# axiom_beta_plugin_module_TE0714_SDI_v0_7.net
KiCad netlist of a schematic drawn in EAGLE
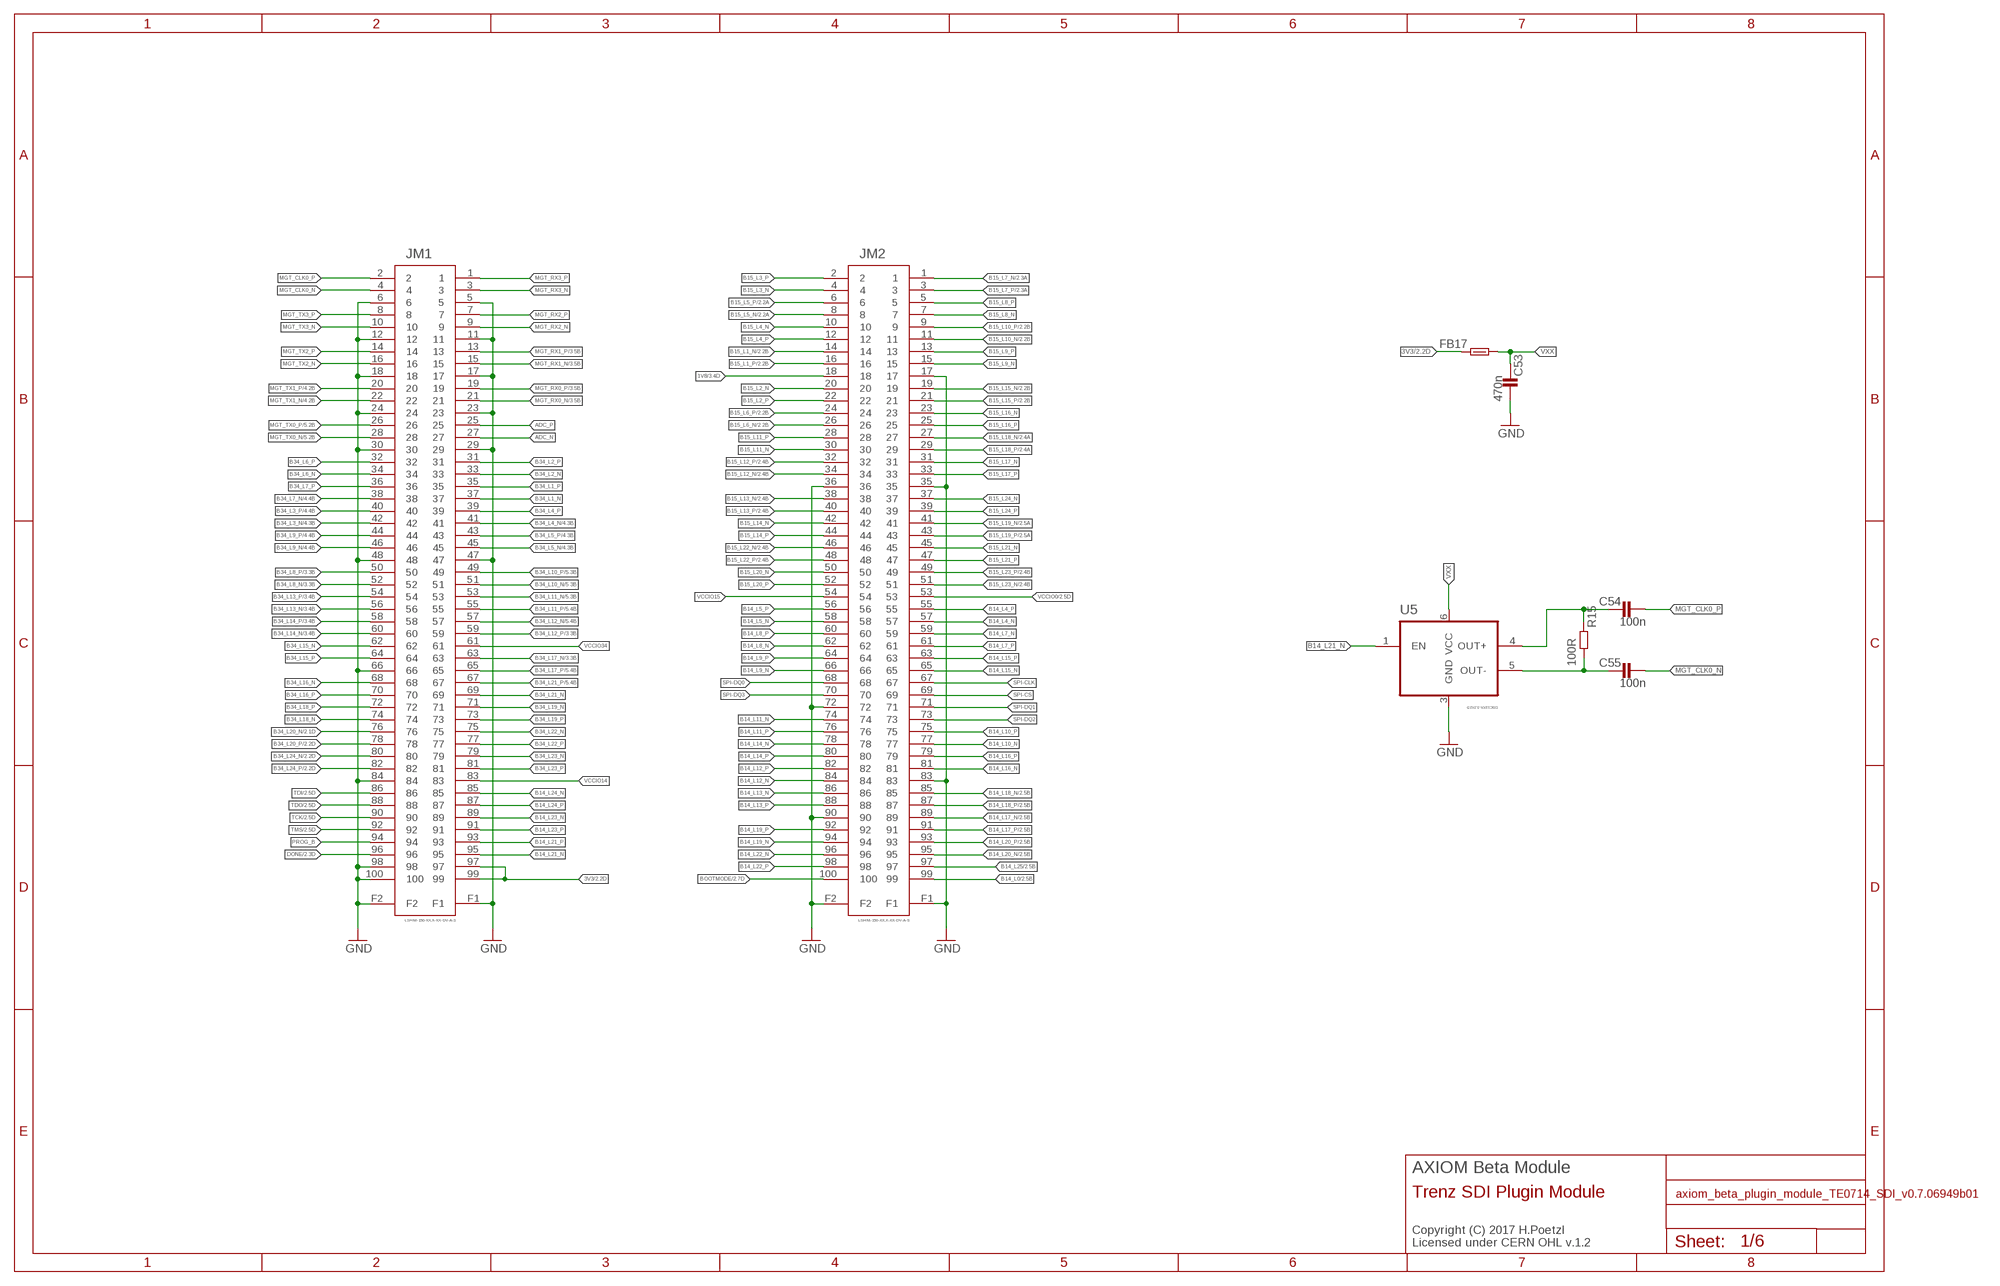
[diagram p0: schematic, sheet 1]
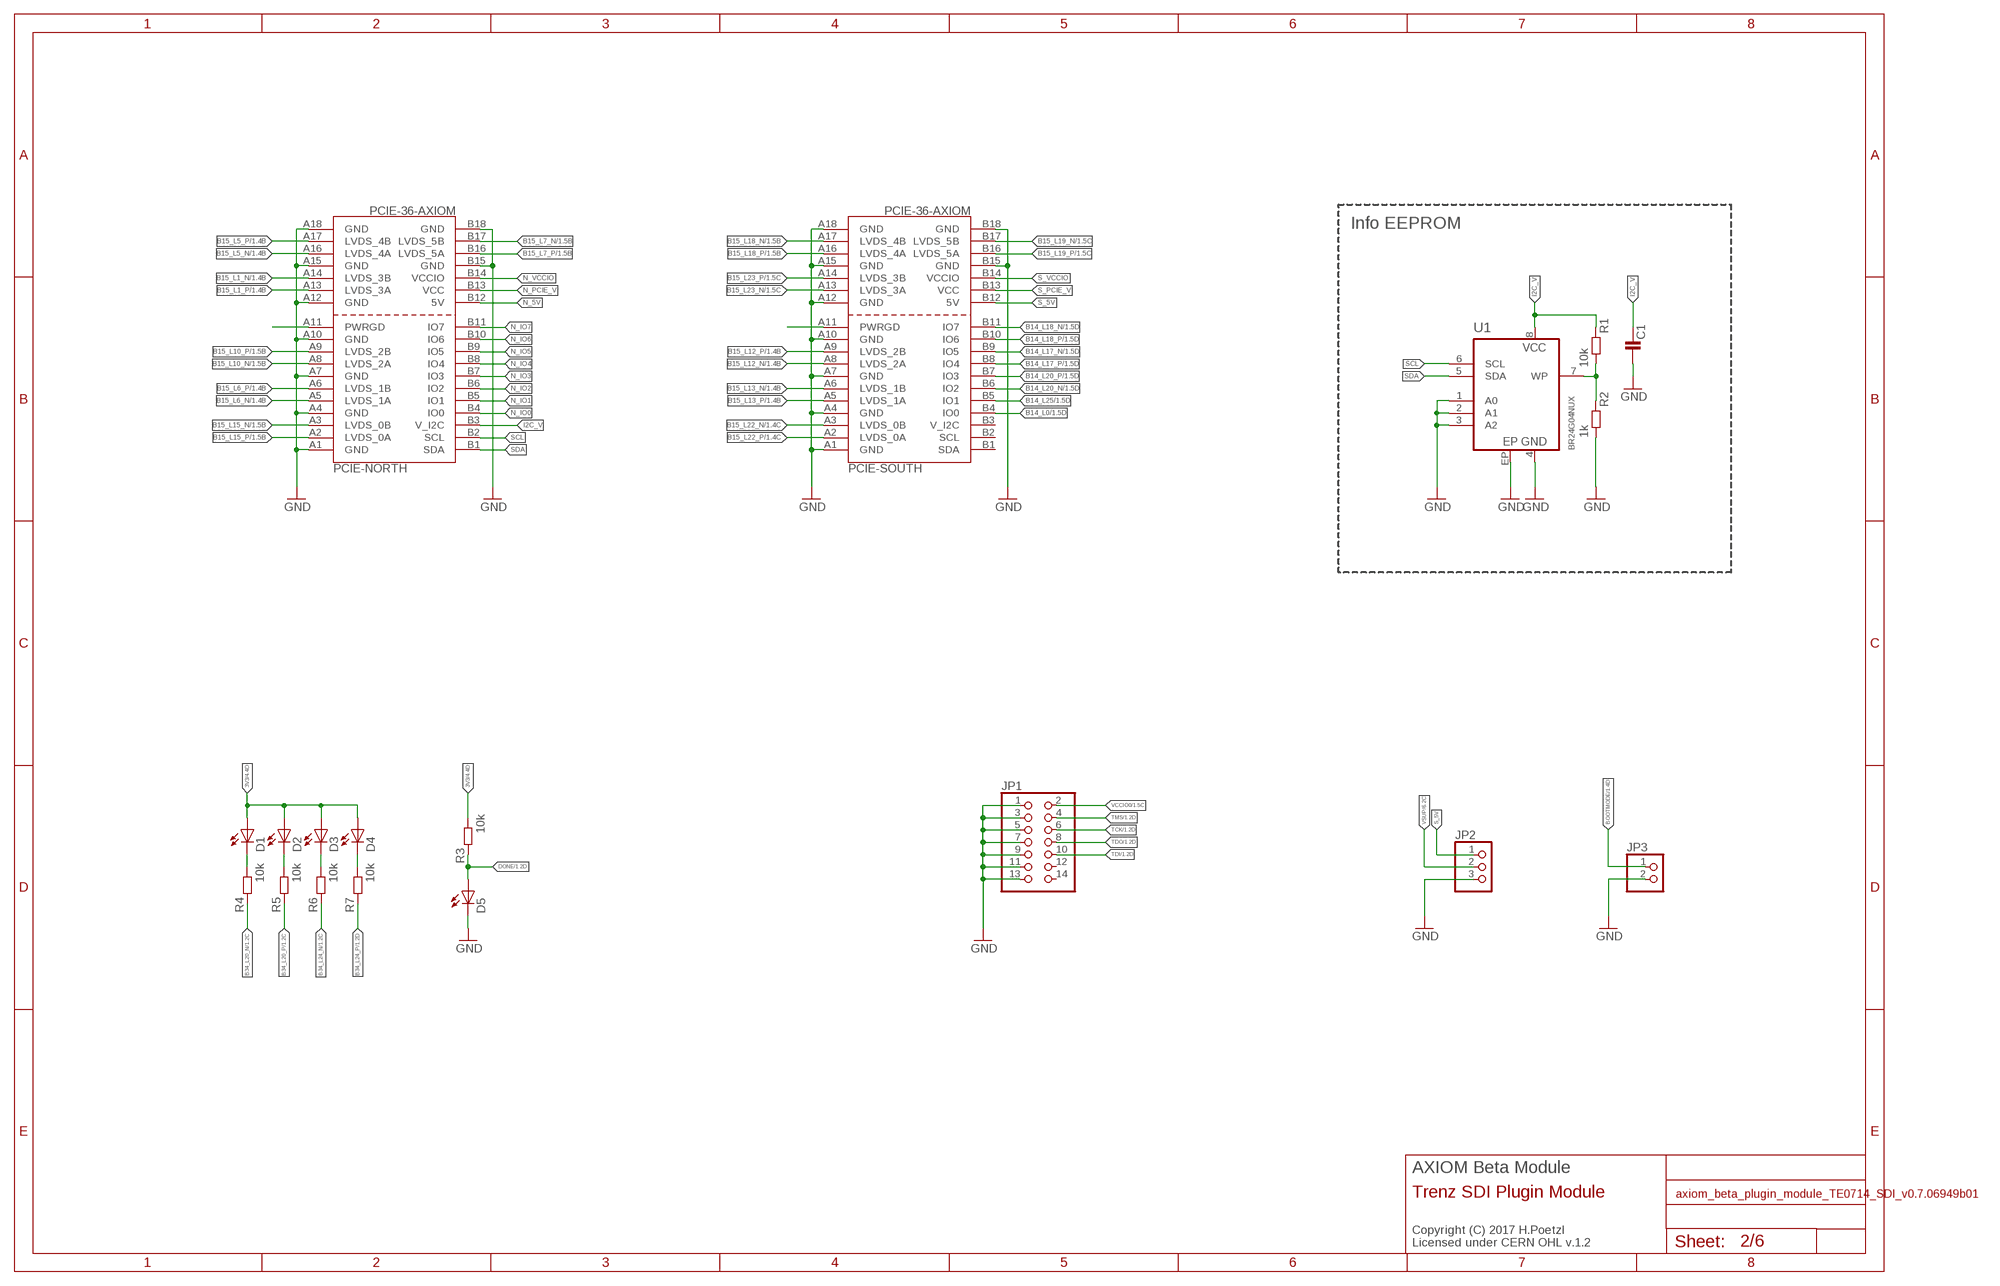
[diagram p1: schematic, sheet 2]
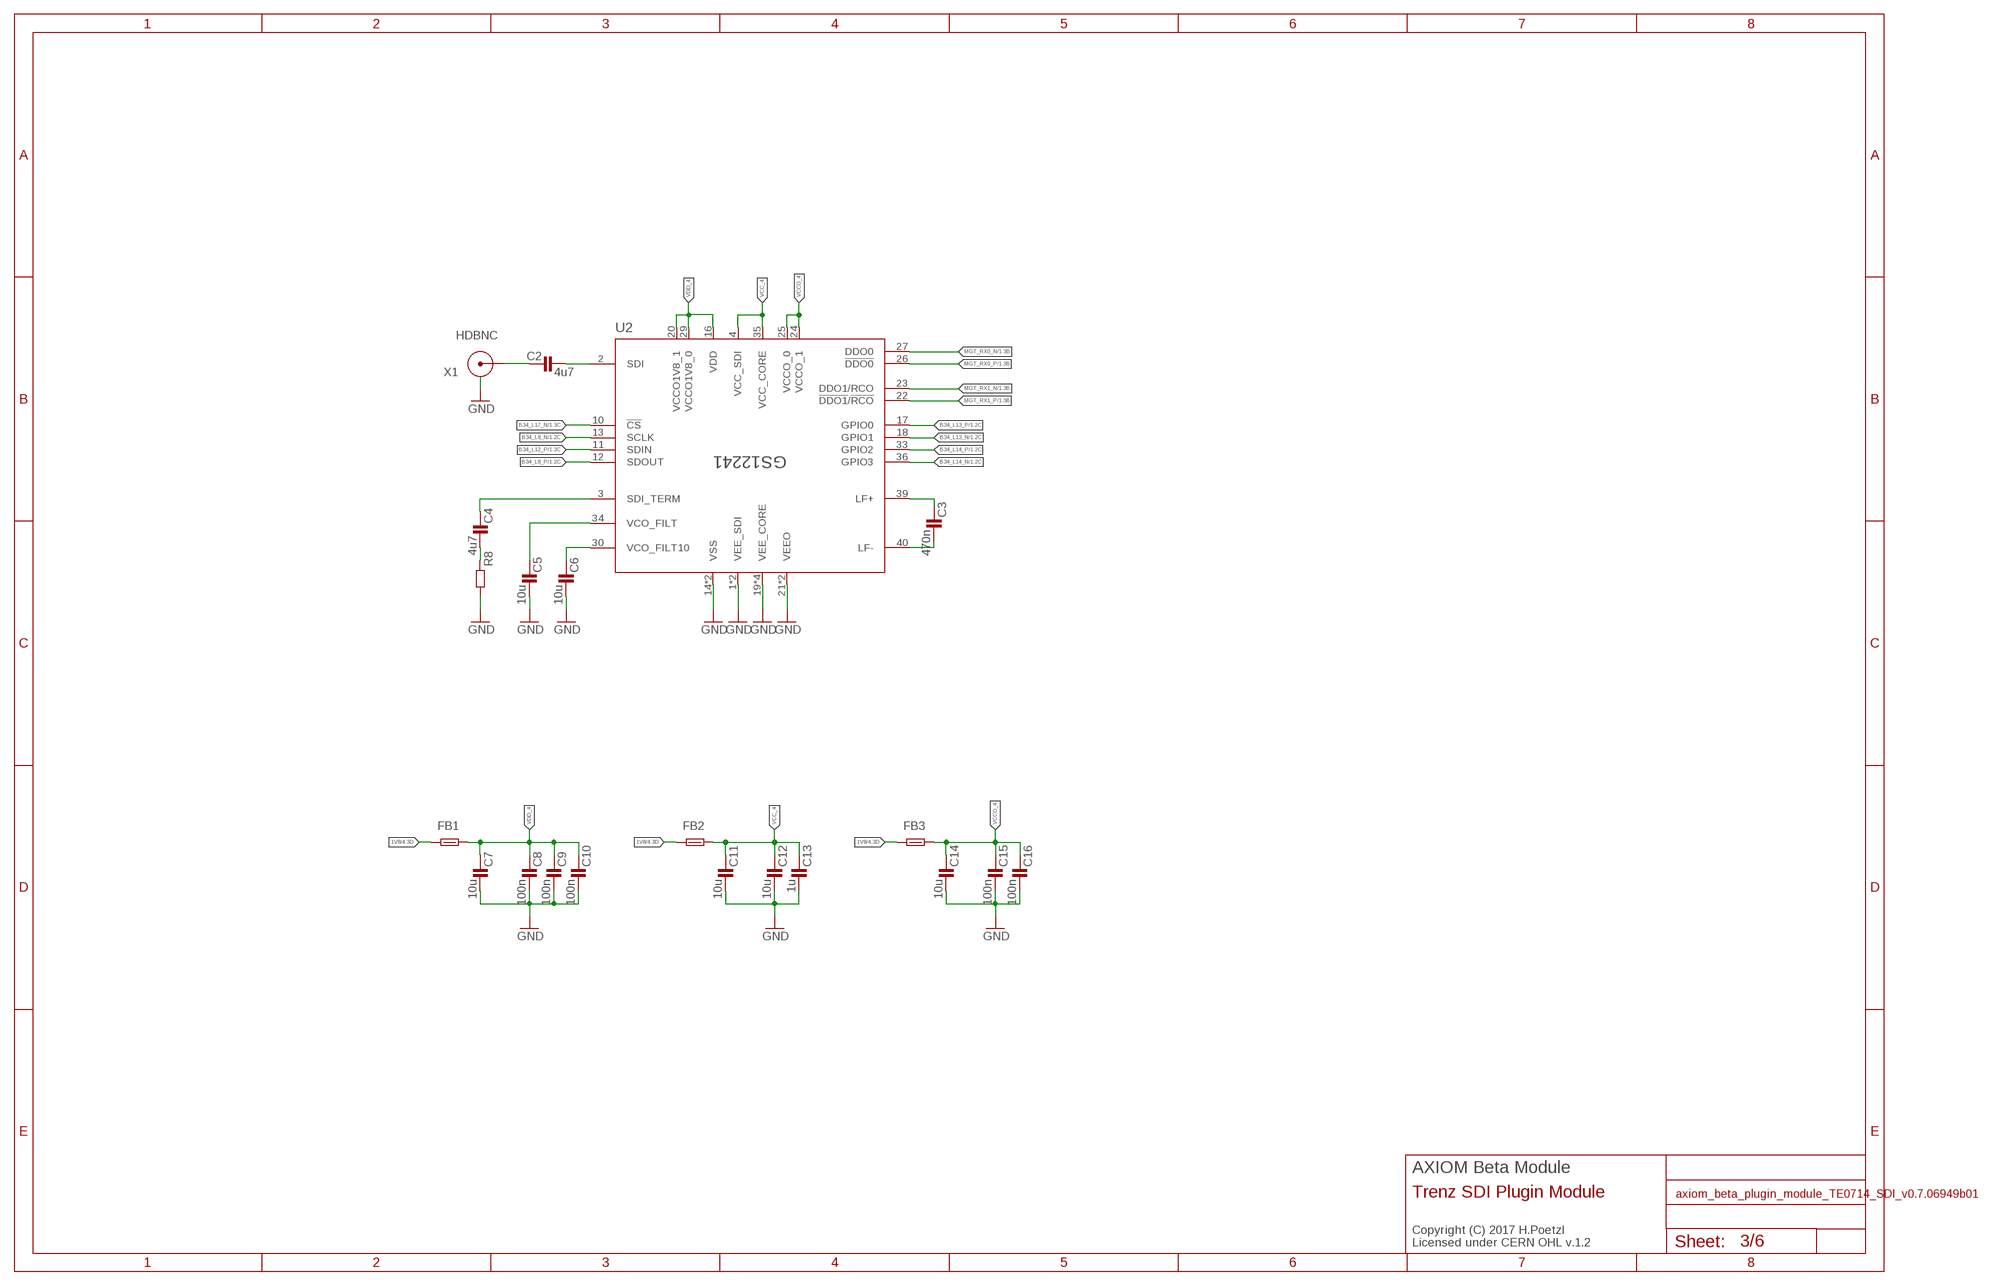
[diagram p2: schematic, sheet 3]
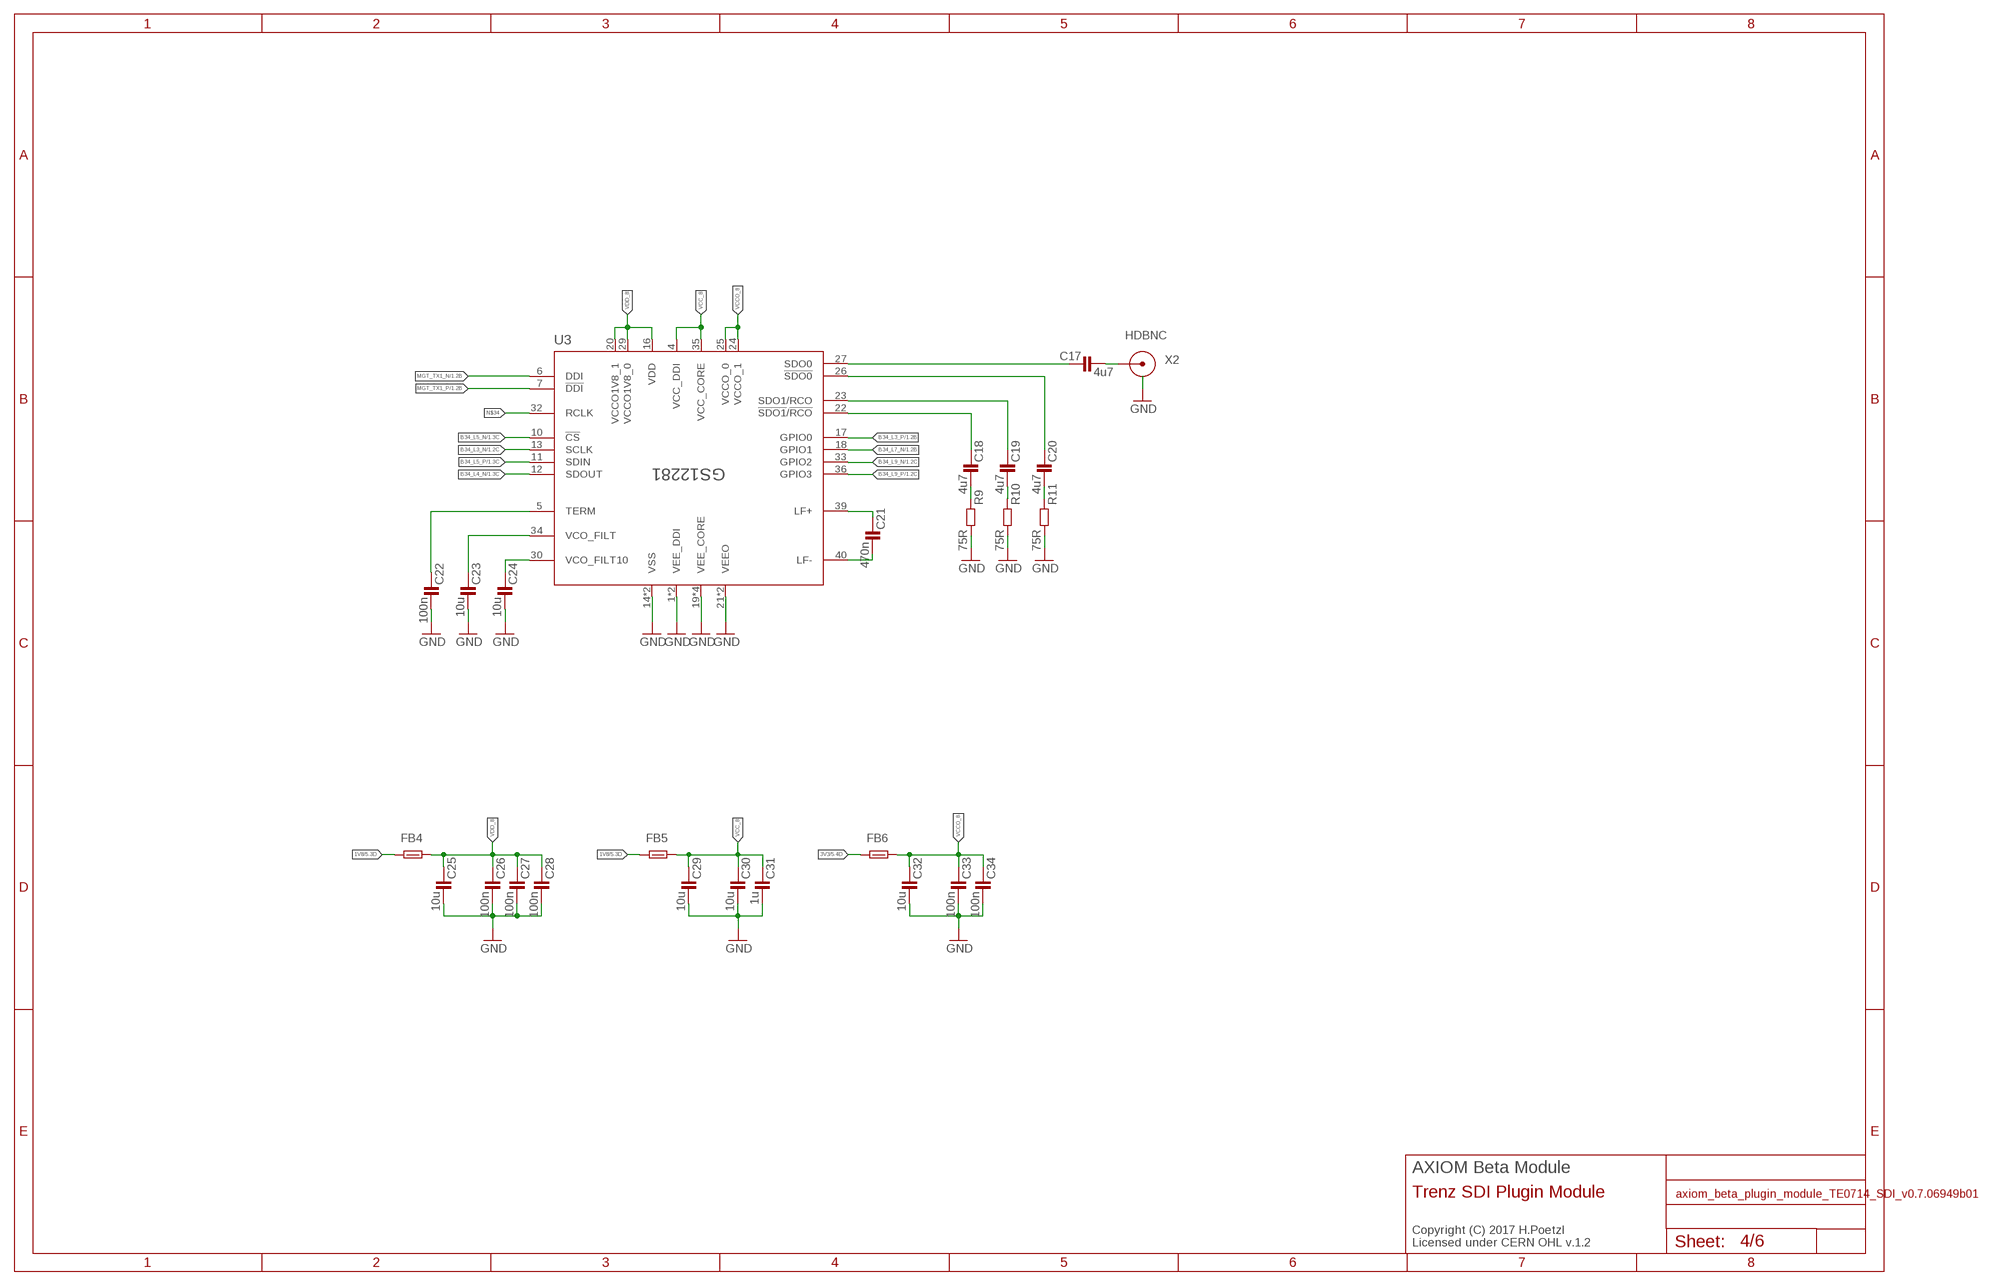
[diagram p3: schematic, sheet 4]
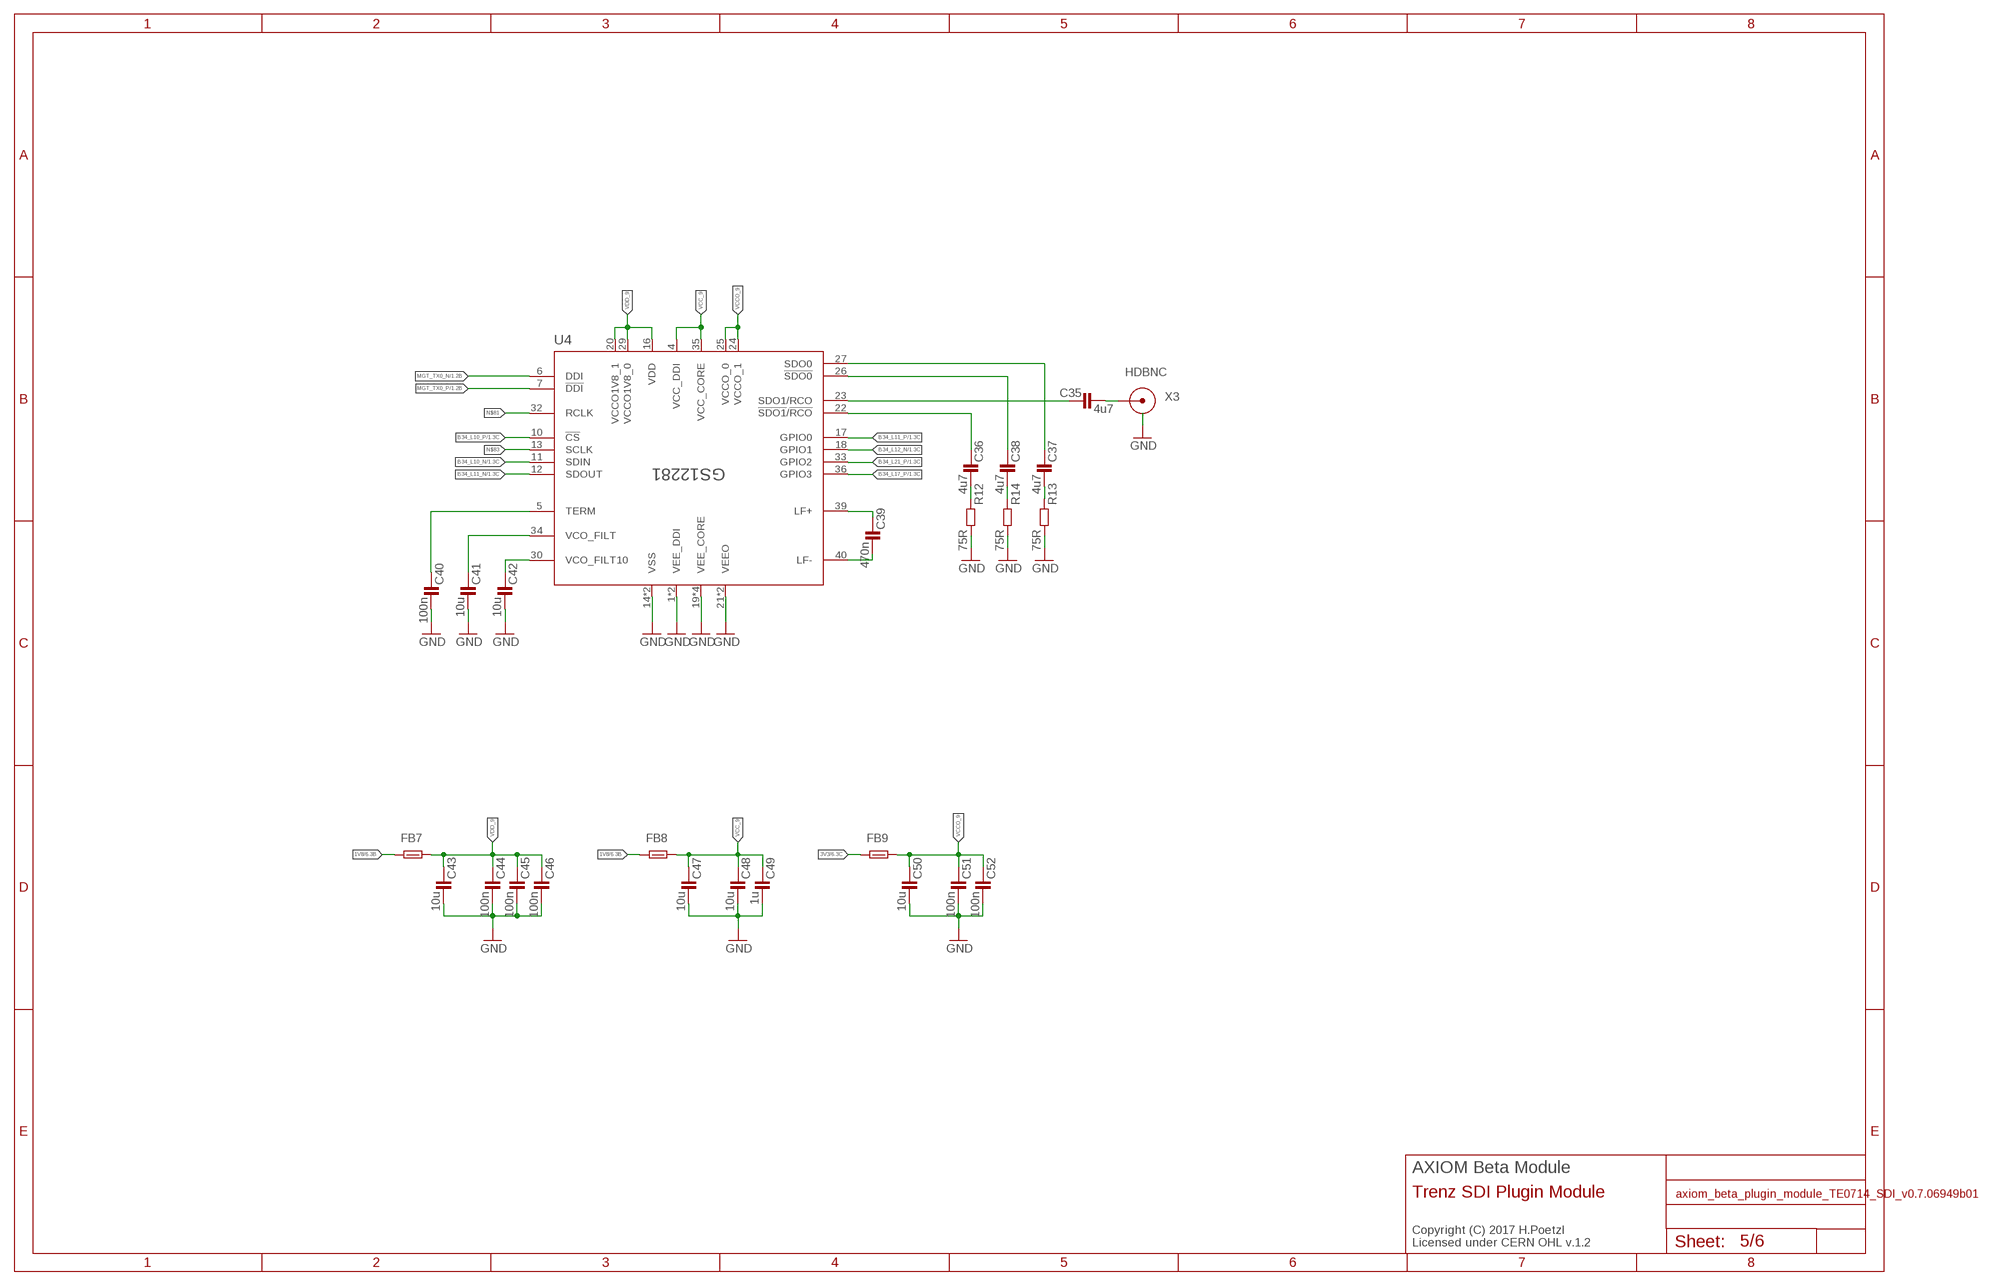
[diagram p4: schematic, sheet 5]
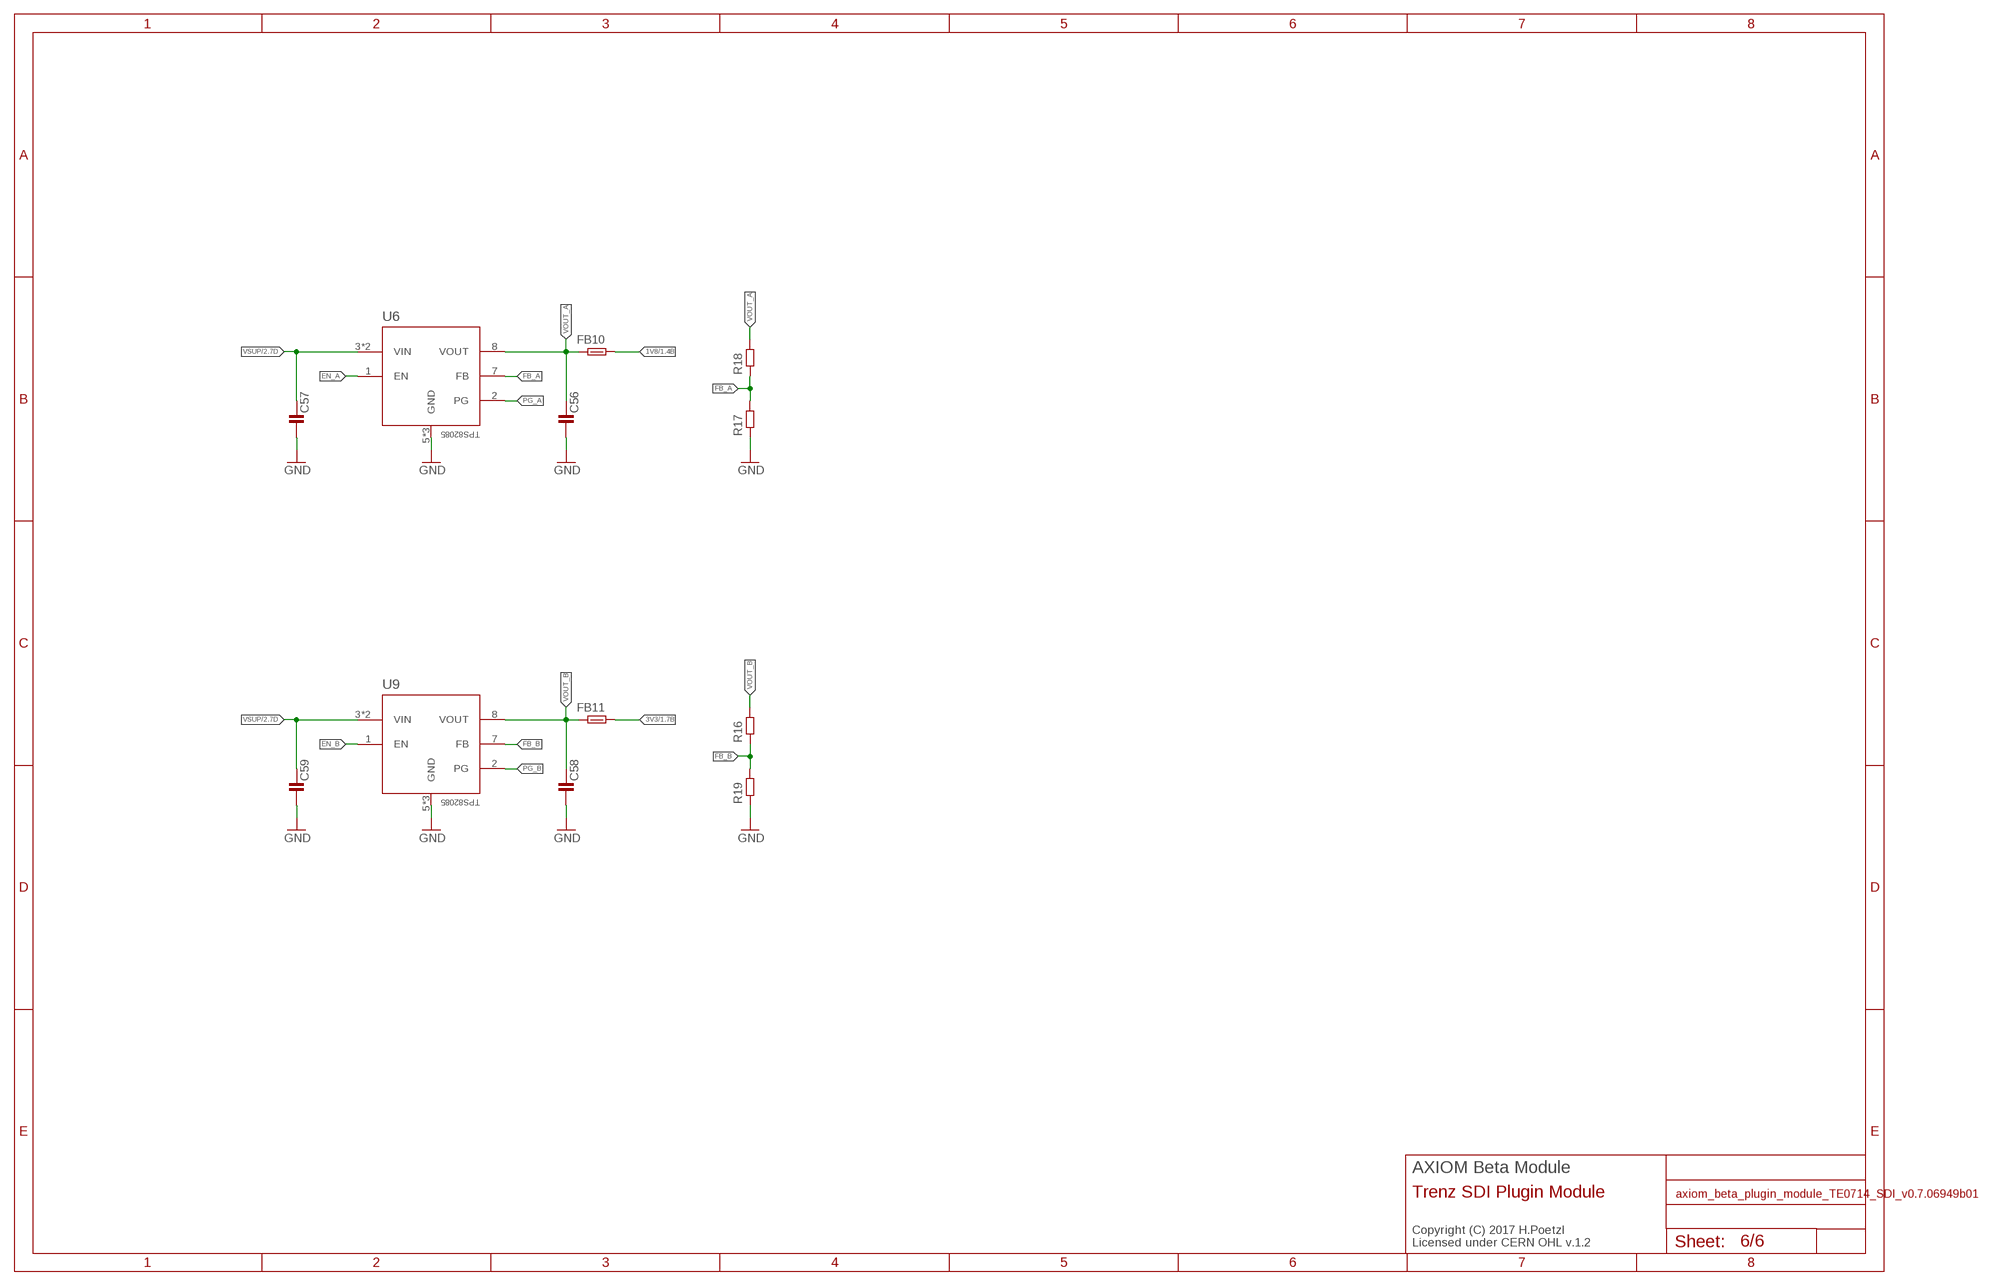
[diagram p5: schematic, sheet 6]

(export (version "E")
  (design (tool "Eeschema 10.0.6"))
  (components
    (comp (ref "C17")
      (value "4u7")
      (footprint "eagle-import:0402-C")
      (libsource (lib "eagle-import") (part "C0402-C"))
    )
    (comp (ref "C18")
      (value "4u7")
      (footprint "eagle-import:0402-C")
      (libsource (lib "eagle-import") (part "C0402-C"))
    )
    (comp (ref "C19")
      (value "4u7")
      (footprint "eagle-import:0402-C")
      (libsource (lib "eagle-import") (part "C0402-C"))
    )
    (comp (ref "C20")
      (value "4u7")
      (footprint "eagle-import:0402-C")
      (libsource (lib "eagle-import") (part "C0402-C"))
    )
    (comp (ref "C21")
      (value "470n")
      (footprint "eagle-import:0201-C")
      (libsource (lib "eagle-import") (part "C0201-C"))
    )
    (comp (ref "C22")
      (value "100n")
      (footprint "eagle-import:0201-C")
      (libsource (lib "eagle-import") (part "C0201-C"))
    )
    (comp (ref "C23")
      (value "10u")
      (footprint "eagle-import:0201-C")
      (libsource (lib "eagle-import") (part "C0201-C"))
    )
    (comp (ref "C24")
      (value "10u")
      (footprint "eagle-import:0402-C")
      (libsource (lib "eagle-import") (part "C0402-C"))
    )
    (comp (ref "C25")
      (value "10u")
      (footprint "eagle-import:0402-C")
      (libsource (lib "eagle-import") (part "C0402-C"))
    )
    (comp (ref "C26")
      (value "100n")
      (footprint "eagle-import:0201-C")
      (libsource (lib "eagle-import") (part "C0201-C"))
    )
    (comp (ref "C27")
      (value "100n")
      (footprint "eagle-import:0201-C")
      (libsource (lib "eagle-import") (part "C0201-C"))
    )
    (comp (ref "C28")
      (value "100n")
      (footprint "eagle-import:0201-C")
      (libsource (lib "eagle-import") (part "C0201-C"))
    )
    (comp (ref "C29")
      (value "10u")
      (footprint "eagle-import:0402-C")
      (libsource (lib "eagle-import") (part "C0402-C"))
    )
    (comp (ref "C30")
      (value "10u")
      (footprint "eagle-import:0402-C")
      (libsource (lib "eagle-import") (part "C0402-C"))
    )
    (comp (ref "C31")
      (value "1u")
      (footprint "eagle-import:0201-C")
      (libsource (lib "eagle-import") (part "C0201-C"))
    )
    (comp (ref "C32")
      (value "10u")
      (footprint "eagle-import:0402-C")
      (libsource (lib "eagle-import") (part "C0402-C"))
    )
    (comp (ref "C33")
      (value "100n")
      (footprint "eagle-import:0201-C")
      (libsource (lib "eagle-import") (part "C0201-C"))
    )
    (comp (ref "C34")
      (value "100n")
      (footprint "eagle-import:0201-C")
      (libsource (lib "eagle-import") (part "C0201-C"))
    )
    (comp (ref "FB4")
      (value "FB0402-C")
      (footprint "eagle-import:0402-C")
      (libsource (lib "eagle-import") (part "FB0402-C"))
    )
    (comp (ref "FB5")
      (value "FB0402-C")
      (footprint "eagle-import:0402-C")
      (libsource (lib "eagle-import") (part "FB0402-C"))
    )
    (comp (ref "FB6")
      (value "FB0402-C")
      (footprint "eagle-import:0402-C")
      (libsource (lib "eagle-import") (part "FB0402-C"))
    )
    (comp (ref "R9")
      (value "75R")
      (footprint "eagle-import:0201-C")
      (libsource (lib "eagle-import") (part "R0201-C"))
    )
    (comp (ref "R10")
      (value "75R")
      (footprint "eagle-import:0201-C")
      (libsource (lib "eagle-import") (part "R0201-C"))
    )
    (comp (ref "R11")
      (value "75R")
      (footprint "eagle-import:0201-C")
      (libsource (lib "eagle-import") (part "R0201-C"))
    )
    (comp (ref "U3")
      (value "GS12281")
      (footprint "eagle-import:UQFN40P600X400X100-41N")
      (libsource (lib "eagle-import") (part "GS12281"))
    )
    (comp (ref "X2")
      (value "HDBNC")
      (footprint "eagle-import:HDBNC_EDGE_2SIDE")
      (libsource (lib "eagle-import") (part "HDBNC"))
    )
    (comp (ref "C1")
      (value "C0402-B")
      (footprint "eagle-import:0402-B")
      (libsource (lib "eagle-import") (part "C0402-B"))
    )
    (comp (ref "D1")
      (value "LED")
      (footprint "eagle-import:CHIPLED_0603")
      (libsource (lib "eagle-import") (part "LED"))
    )
    (comp (ref "D2")
      (value "LED")
      (footprint "eagle-import:CHIPLED_0603")
      (libsource (lib "eagle-import") (part "LED"))
    )
    (comp (ref "D3")
      (value "LED")
      (footprint "eagle-import:CHIPLED_0603")
      (libsource (lib "eagle-import") (part "LED"))
    )
    (comp (ref "D4")
      (value "LED")
      (footprint "eagle-import:CHIPLED_0603")
      (libsource (lib "eagle-import") (part "LED"))
    )
    (comp (ref "D5")
      (value "LED")
      (footprint "eagle-import:CHIPLED_0603")
      (libsource (lib "eagle-import") (part "LED"))
    )
    (comp (ref "JP1")
      (value "PINHD-2X07_2.00")
      (footprint "eagle-import:2X07M")
      (libsource (lib "eagle-import") (part "PINHD-2X07_2.00"))
    )
    (comp (ref "JP2")
      (value "PINHD-1X03_2.54-90°-S")
      (footprint "eagle-import:1X03_90-S")
      (libsource (lib "eagle-import") (part "PINHD-1X03_2.54-90°-S"))
    )
    (comp (ref "JP3")
      (value "PINHD-1X02_2.54-S")
      (footprint "eagle-import:1X02-S")
      (libsource (lib "eagle-import") (part "PINHD-1X02_2.54-S"))
    )
    (comp (ref "PCIE-NORTH")
      (value "PCIE-36-AXIOM")
      (footprint "eagle-import:PCIE-36-AXIOM")
      (libsource (lib "eagle-import") (part "PCIE-36-AXIOM"))
    )
    (comp (ref "PCIE-SOUTH")
      (value "PCIE-36-AXIOM")
      (footprint "eagle-import:PCIE-36-AXIOM")
      (libsource (lib "eagle-import") (part "PCIE-36-AXIOM"))
    )
    (comp (ref "R1")
      (value "10k")
      (footprint "eagle-import:0402-B")
      (libsource (lib "eagle-import") (part "R0402-B"))
    )
    (comp (ref "R2")
      (value "1k")
      (footprint "eagle-import:0402-B")
      (libsource (lib "eagle-import") (part "R0402-B"))
    )
    (comp (ref "R3")
      (value "10k")
      (footprint "eagle-import:0402-C")
      (libsource (lib "eagle-import") (part "R0402-C"))
    )
    (comp (ref "R4")
      (value "10k")
      (footprint "eagle-import:0402-C")
      (libsource (lib "eagle-import") (part "R0402-C"))
    )
    (comp (ref "R5")
      (value "10k")
      (footprint "eagle-import:0402-C")
      (libsource (lib "eagle-import") (part "R0402-C"))
    )
    (comp (ref "R6")
      (value "10k")
      (footprint "eagle-import:0402-C")
      (libsource (lib "eagle-import") (part "R0402-C"))
    )
    (comp (ref "R7")
      (value "10k")
      (footprint "eagle-import:0402-C")
      (libsource (lib "eagle-import") (part "R0402-C"))
    )
    (comp (ref "U1")
      (value "BR24G04NUX")
      (footprint "eagle-import:DFN200X300X100-9N")
      (libsource (lib "eagle-import") (part "BR24G04NUX"))
    )
    (comp (ref "C2")
      (value "4u7")
      (footprint "eagle-import:0402-C")
      (libsource (lib "eagle-import") (part "C0402-C"))
    )
    (comp (ref "C3")
      (value "470n")
      (footprint "eagle-import:0201-C")
      (libsource (lib "eagle-import") (part "C0201-C"))
    )
    (comp (ref "C4")
      (value "4u7")
      (footprint "eagle-import:0402-C")
      (libsource (lib "eagle-import") (part "C0402-C"))
    )
    (comp (ref "C5")
      (value "10u")
      (footprint "eagle-import:0201-C")
      (libsource (lib "eagle-import") (part "C0201-C"))
    )
    (comp (ref "C6")
      (value "10u")
      (footprint "eagle-import:0402-C")
      (libsource (lib "eagle-import") (part "C0402-C"))
    )
    (comp (ref "C7")
      (value "10u")
      (footprint "eagle-import:0402-C")
      (libsource (lib "eagle-import") (part "C0402-C"))
    )
    (comp (ref "C8")
      (value "100n")
      (footprint "eagle-import:0201-C")
      (libsource (lib "eagle-import") (part "C0201-C"))
    )
    (comp (ref "C9")
      (value "100n")
      (footprint "eagle-import:0201-C")
      (libsource (lib "eagle-import") (part "C0201-C"))
    )
    (comp (ref "C10")
      (value "100n")
      (footprint "eagle-import:0201-C")
      (libsource (lib "eagle-import") (part "C0201-C"))
    )
    (comp (ref "C11")
      (value "10u")
      (footprint "eagle-import:0402-C")
      (libsource (lib "eagle-import") (part "C0402-C"))
    )
    (comp (ref "C12")
      (value "10u")
      (footprint "eagle-import:0402-C")
      (libsource (lib "eagle-import") (part "C0402-C"))
    )
    (comp (ref "C13")
      (value "1u")
      (footprint "eagle-import:0201-C")
      (libsource (lib "eagle-import") (part "C0201-C"))
    )
    (comp (ref "C14")
      (value "10u")
      (footprint "eagle-import:0402-C")
      (libsource (lib "eagle-import") (part "C0402-C"))
    )
    (comp (ref "C15")
      (value "100n")
      (footprint "eagle-import:0201-C")
      (libsource (lib "eagle-import") (part "C0201-C"))
    )
    (comp (ref "C16")
      (value "100n")
      (footprint "eagle-import:0201-C")
      (libsource (lib "eagle-import") (part "C0201-C"))
    )
    (comp (ref "FB1")
      (value "FB0402-C")
      (footprint "eagle-import:0402-C")
      (libsource (lib "eagle-import") (part "FB0402-C"))
    )
    (comp (ref "FB2")
      (value "FB0402-C")
      (footprint "eagle-import:0402-C")
      (libsource (lib "eagle-import") (part "FB0402-C"))
    )
    (comp (ref "FB3")
      (value "FB0402-C")
      (footprint "eagle-import:0402-C")
      (libsource (lib "eagle-import") (part "FB0402-C"))
    )
    (comp (ref "R8")
      (value "R0201-C")
      (footprint "eagle-import:0201-C")
      (libsource (lib "eagle-import") (part "R0201-C"))
    )
    (comp (ref "U2")
      (value "GS12241")
      (footprint "eagle-import:UQFN40P600X400X100-41N")
      (libsource (lib "eagle-import") (part "GS12241"))
    )
    (comp (ref "X1")
      (value "HDBNC")
      (footprint "eagle-import:HDBNC_EDGE_2SIDE")
      (libsource (lib "eagle-import") (part "HDBNC"))
    )
    (comp (ref "C53")
      (value "470n")
      (footprint "eagle-import:0402-C")
      (libsource (lib "eagle-import") (part "C0402-C"))
    )
    (comp (ref "C54")
      (value "100n")
      (footprint "eagle-import:0201-C")
      (libsource (lib "eagle-import") (part "C0201-C"))
    )
    (comp (ref "C55")
      (value "100n")
      (footprint "eagle-import:0201-C")
      (libsource (lib "eagle-import") (part "C0201-C"))
    )
    (comp (ref "FB17")
      (value "FB0402-C")
      (footprint "eagle-import:0402-C")
      (libsource (lib "eagle-import") (part "FB0402-C"))
    )
    (comp (ref "JM1")
      (value "LSHM-150-XX.X-XX-DV-A-S")
      (footprint "eagle-import:LSHM-150-XX.X-XX-DV-A-S")
      (libsource (lib "eagle-import") (part "LSHM-150-XX.X-XX-DV-A-S"))
    )
    (comp (ref "JM2")
      (value "LSHM-150-XX.X-XX-DV-A-S")
      (footprint "eagle-import:LSHM-150-XX.X-XX-DV-A-S")
      (libsource (lib "eagle-import") (part "LSHM-150-XX.X-XX-DV-A-S"))
    )
    (comp (ref "R15")
      (value "100R")
      (footprint "eagle-import:0201-C")
      (libsource (lib "eagle-import") (part "R0201-C"))
    )
    (comp (ref "U5")
      (value "DSC11XX-3.2X2.5")
      (footprint "eagle-import:3.2X2.5")
      (libsource (lib "eagle-import") (part "DSC11XX-3.2X2.5"))
    )
    (comp (ref "C56")
      (value "C0603-C")
      (footprint "eagle-import:0603-C")
      (libsource (lib "eagle-import") (part "C0603-C"))
    )
    (comp (ref "C57")
      (value "C0603-C")
      (footprint "eagle-import:0603-C")
      (libsource (lib "eagle-import") (part "C0603-C"))
    )
    (comp (ref "C58")
      (value "C0603-C")
      (footprint "eagle-import:0603-C")
      (libsource (lib "eagle-import") (part "C0603-C"))
    )
    (comp (ref "C59")
      (value "C0603-C")
      (footprint "eagle-import:0603-C")
      (libsource (lib "eagle-import") (part "C0603-C"))
    )
    (comp (ref "FB10")
      (value "FB0603-C")
      (footprint "eagle-import:0603-C")
      (libsource (lib "eagle-import") (part "FB0603-C"))
    )
    (comp (ref "FB11")
      (value "FB0603-C")
      (footprint "eagle-import:0603-C")
      (libsource (lib "eagle-import") (part "FB0603-C"))
    )
    (comp (ref "R16")
      (value "R0201-C")
      (footprint "eagle-import:0201-C")
      (libsource (lib "eagle-import") (part "R0201-C"))
    )
    (comp (ref "R17")
      (value "R0201-C")
      (footprint "eagle-import:0201-C")
      (libsource (lib "eagle-import") (part "R0201-C"))
    )
    (comp (ref "R18")
      (value "R0201-C")
      (footprint "eagle-import:0201-C")
      (libsource (lib "eagle-import") (part "R0201-C"))
    )
    (comp (ref "R19")
      (value "R0201-C")
      (footprint "eagle-import:0201-C")
      (libsource (lib "eagle-import") (part "R0201-C"))
    )
    (comp (ref "U6")
      (value "TPS82085")
      (footprint "eagle-import:MICROSIP")
      (libsource (lib "eagle-import") (part "TPS82085"))
    )
    (comp (ref "U9")
      (value "TPS82085")
      (footprint "eagle-import:MICROSIP")
      (libsource (lib "eagle-import") (part "TPS82085"))
    )
    (comp (ref "C35")
      (value "4u7")
      (footprint "eagle-import:0402-C")
      (libsource (lib "eagle-import") (part "C0402-C"))
    )
    (comp (ref "C36")
      (value "4u7")
      (footprint "eagle-import:0402-C")
      (libsource (lib "eagle-import") (part "C0402-C"))
    )
    (comp (ref "C37")
      (value "4u7")
      (footprint "eagle-import:0402-C")
      (libsource (lib "eagle-import") (part "C0402-C"))
    )
    (comp (ref "C38")
      (value "4u7")
      (footprint "eagle-import:0402-C")
      (libsource (lib "eagle-import") (part "C0402-C"))
    )
    (comp (ref "C39")
      (value "470n")
      (footprint "eagle-import:0201-C")
      (libsource (lib "eagle-import") (part "C0201-C"))
    )
    (comp (ref "C40")
      (value "100n")
      (footprint "eagle-import:0201-C")
      (libsource (lib "eagle-import") (part "C0201-C"))
    )
    (comp (ref "C41")
      (value "10u")
      (footprint "eagle-import:0402-C")
      (libsource (lib "eagle-import") (part "C0402-C"))
    )
    (comp (ref "C42")
      (value "10u")
      (footprint "eagle-import:0402-C")
      (libsource (lib "eagle-import") (part "C0402-C"))
    )
    (comp (ref "C43")
      (value "10u")
      (footprint "eagle-import:0402-C")
      (libsource (lib "eagle-import") (part "C0402-C"))
    )
    (comp (ref "C44")
      (value "100n")
      (footprint "eagle-import:0201-C")
      (libsource (lib "eagle-import") (part "C0201-C"))
    )
    (comp (ref "C45")
      (value "100n")
      (footprint "eagle-import:0201-C")
      (libsource (lib "eagle-import") (part "C0201-C"))
    )
    (comp (ref "C46")
      (value "100n")
      (footprint "eagle-import:0201-C")
      (libsource (lib "eagle-import") (part "C0201-C"))
    )
    (comp (ref "C47")
      (value "10u")
      (footprint "eagle-import:0402-C")
      (libsource (lib "eagle-import") (part "C0402-C"))
    )
    (comp (ref "C48")
      (value "10u")
      (footprint "eagle-import:0402-C")
      (libsource (lib "eagle-import") (part "C0402-C"))
    )
    (comp (ref "C49")
      (value "1u")
      (footprint "eagle-import:0201-C")
      (libsource (lib "eagle-import") (part "C0201-C"))
    )
    (comp (ref "C50")
      (value "10u")
      (footprint "eagle-import:0402-C")
      (libsource (lib "eagle-import") (part "C0402-C"))
    )
    (comp (ref "C51")
      (value "100n")
      (footprint "eagle-import:0201-C")
      (libsource (lib "eagle-import") (part "C0201-C"))
    )
    (comp (ref "C52")
      (value "100n")
      (footprint "eagle-import:0201-C")
      (libsource (lib "eagle-import") (part "C0201-C"))
    )
    (comp (ref "FB7")
      (value "FB0402-C")
      (footprint "eagle-import:0402-C")
      (libsource (lib "eagle-import") (part "FB0402-C"))
    )
    (comp (ref "FB8")
      (value "FB0402-C")
      (footprint "eagle-import:0402-C")
      (libsource (lib "eagle-import") (part "FB0402-C"))
    )
    (comp (ref "FB9")
      (value "FB0402-C")
      (footprint "eagle-import:0402-C")
      (libsource (lib "eagle-import") (part "FB0402-C"))
    )
    (comp (ref "R12")
      (value "75R")
      (footprint "eagle-import:0201-C")
      (libsource (lib "eagle-import") (part "R0201-C"))
    )
    (comp (ref "R13")
      (value "75R")
      (footprint "eagle-import:0201-C")
      (libsource (lib "eagle-import") (part "R0201-C"))
    )
    (comp (ref "R14")
      (value "75R")
      (footprint "eagle-import:0201-C")
      (libsource (lib "eagle-import") (part "R0201-C"))
    )
    (comp (ref "U4")
      (value "GS12281")
      (footprint "eagle-import:UQFN40P600X400X100-41N")
      (libsource (lib "eagle-import") (part "GS12281"))
    )
    (comp (ref "X3")
      (value "HDBNC")
      (footprint "eagle-import:HDBNC_EDGE_2SIDE")
      (libsource (lib "eagle-import") (part "HDBNC"))
    )
  )
  (nets
    (net (code "1") (name "1V8") (class "Default")
      (node (ref "FB1") (pin "1") (pinfunction "1_1") (pintype "passive"))
      (node (ref "FB10") (pin "2") (pinfunction "2_2") (pintype "passive"))
      (node (ref "FB2") (pin "1") (pinfunction "1_1") (pintype "passive"))
      (node (ref "FB3") (pin "1") (pinfunction "1_1") (pintype "passive"))
      (node (ref "FB4") (pin "1") (pinfunction "1_1") (pintype "passive"))
      (node (ref "FB5") (pin "1") (pinfunction "1_1") (pintype "passive"))
      (node (ref "FB7") (pin "1") (pinfunction "1_1") (pintype "passive"))
      (node (ref "FB8") (pin "1") (pinfunction "1_1") (pintype "passive"))
      (node (ref "JM2") (pin "18") (pinfunction "18_18") (pintype "bidirectional"))
    )
    (net (code "2") (name "3V3") (class "Default")
      (node (ref "D1") (pin "A") (pinfunction "A_A") (pintype "passive"))
      (node (ref "D2") (pin "A") (pinfunction "A_A") (pintype "passive"))
      (node (ref "D3") (pin "A") (pinfunction "A_A") (pintype "passive"))
      (node (ref "D4") (pin "A") (pinfunction "A_A") (pintype "passive"))
      (node (ref "FB11") (pin "2") (pinfunction "2_2") (pintype "passive"))
      (node (ref "FB17") (pin "1") (pinfunction "1_1") (pintype "passive"))
      (node (ref "FB6") (pin "1") (pinfunction "1_1") (pintype "passive"))
      (node (ref "FB9") (pin "1") (pinfunction "1_1") (pintype "passive"))
      (node (ref "JM1") (pin "97") (pinfunction "97_97") (pintype "bidirectional"))
      (node (ref "JM1") (pin "99") (pinfunction "99_99") (pintype "bidirectional"))
      (node (ref "R3") (pin "2") (pinfunction "2_2") (pintype "passive"))
    )
    (net (code "3") (name "ADC_N") (class "Default")
      (node (ref "JM1") (pin "27") (pinfunction "27_27") (pintype "bidirectional"))
    )
    (net (code "4") (name "ADC_P") (class "Default")
      (node (ref "JM1") (pin "25") (pinfunction "25_25") (pintype "bidirectional"))
    )
    (net (code "5") (name "B14_L0") (class "Default")
      (node (ref "JM2") (pin "99") (pinfunction "99_99") (pintype "bidirectional"))
      (node (ref "PCIE-SOUTH") (pin "B4") (pinfunction "IO0_B4") (pintype "passive"))
    )
    (net (code "6") (name "B14_L4_N") (class "Default")
      (node (ref "JM2") (pin "57") (pinfunction "57_57") (pintype "bidirectional"))
    )
    (net (code "7") (name "B14_L4_P") (class "Default")
      (node (ref "JM2") (pin "55") (pinfunction "55_55") (pintype "bidirectional"))
    )
    (net (code "8") (name "B14_L5_N") (class "Default")
      (node (ref "JM2") (pin "58") (pinfunction "58_58") (pintype "bidirectional"))
    )
    (net (code "9") (name "B14_L5_P") (class "Default")
      (node (ref "JM2") (pin "56") (pinfunction "56_56") (pintype "bidirectional"))
    )
    (net (code "10") (name "B14_L7_N") (class "Default")
      (node (ref "JM2") (pin "59") (pinfunction "59_59") (pintype "bidirectional"))
    )
    (net (code "11") (name "B14_L7_P") (class "Default")
      (node (ref "JM2") (pin "61") (pinfunction "61_61") (pintype "bidirectional"))
    )
    (net (code "12") (name "B14_L8_N") (class "Default")
      (node (ref "JM2") (pin "62") (pinfunction "62_62") (pintype "bidirectional"))
    )
    (net (code "13") (name "B14_L8_P") (class "Default")
      (node (ref "JM2") (pin "60") (pinfunction "60_60") (pintype "bidirectional"))
    )
    (net (code "14") (name "B14_L9_N") (class "Default")
      (node (ref "JM2") (pin "66") (pinfunction "66_66") (pintype "bidirectional"))
    )
    (net (code "15") (name "B14_L9_P") (class "Default")
      (node (ref "JM2") (pin "64") (pinfunction "64_64") (pintype "bidirectional"))
    )
    (net (code "16") (name "B14_L10_N") (class "Default")
      (node (ref "JM2") (pin "77") (pinfunction "77_77") (pintype "bidirectional"))
    )
    (net (code "17") (name "B14_L10_P") (class "Default")
      (node (ref "JM2") (pin "75") (pinfunction "75_75") (pintype "bidirectional"))
    )
    (net (code "18") (name "B14_L11_N") (class "Default")
      (node (ref "JM2") (pin "74") (pinfunction "74_74") (pintype "bidirectional"))
    )
    (net (code "19") (name "B14_L11_P") (class "Default")
      (node (ref "JM2") (pin "76") (pinfunction "76_76") (pintype "bidirectional"))
    )
    (net (code "20") (name "B14_L12_N") (class "Default")
      (node (ref "JM2") (pin "84") (pinfunction "84_84") (pintype "bidirectional"))
    )
    (net (code "21") (name "B14_L12_P") (class "Default")
      (node (ref "JM2") (pin "82") (pinfunction "82_82") (pintype "bidirectional"))
    )
    (net (code "22") (name "B14_L13_N") (class "Default")
      (node (ref "JM2") (pin "86") (pinfunction "86_86") (pintype "bidirectional"))
    )
    (net (code "23") (name "B14_L13_P") (class "Default")
      (node (ref "JM2") (pin "88") (pinfunction "88_88") (pintype "bidirectional"))
    )
    (net (code "24") (name "B14_L14_N") (class "Default")
      (node (ref "JM2") (pin "78") (pinfunction "78_78") (pintype "bidirectional"))
    )
    (net (code "25") (name "B14_L14_P") (class "Default")
      (node (ref "JM2") (pin "80") (pinfunction "80_80") (pintype "bidirectional"))
    )
    (net (code "26") (name "B14_L15_N") (class "Default")
      (node (ref "JM2") (pin "65") (pinfunction "65_65") (pintype "bidirectional"))
    )
    (net (code "27") (name "B14_L15_P") (class "Default")
      (node (ref "JM2") (pin "63") (pinfunction "63_63") (pintype "bidirectional"))
    )
    (net (code "28") (name "B14_L16_N") (class "Default")
      (node (ref "JM2") (pin "81") (pinfunction "81_81") (pintype "bidirectional"))
    )
    (net (code "29") (name "B14_L16_P") (class "Default")
      (node (ref "JM2") (pin "79") (pinfunction "79_79") (pintype "bidirectional"))
    )
    (net (code "30") (name "B14_L17_N") (class "Default")
      (node (ref "JM2") (pin "89") (pinfunction "89_89") (pintype "bidirectional"))
      (node (ref "PCIE-SOUTH") (pin "B9") (pinfunction "IO5_B9") (pintype "passive"))
    )
    (net (code "31") (name "B14_L17_P") (class "Default")
      (node (ref "JM2") (pin "91") (pinfunction "91_91") (pintype "bidirectional"))
      (node (ref "PCIE-SOUTH") (pin "B8") (pinfunction "IO4_B8") (pintype "passive"))
    )
    (net (code "32") (name "B14_L18_N") (class "Default")
      (node (ref "JM2") (pin "85") (pinfunction "85_85") (pintype "bidirectional"))
      (node (ref "PCIE-SOUTH") (pin "B11") (pinfunction "IO7_B11") (pintype "passive"))
    )
    (net (code "33") (name "B14_L18_P") (class "Default")
      (node (ref "JM2") (pin "87") (pinfunction "87_87") (pintype "bidirectional"))
      (node (ref "PCIE-SOUTH") (pin "B10") (pinfunction "IO6_B10") (pintype "passive"))
    )
    (net (code "34") (name "B14_L19_N") (class "Default")
      (node (ref "JM2") (pin "94") (pinfunction "94_94") (pintype "bidirectional"))
    )
    (net (code "35") (name "B14_L19_P") (class "Default")
      (node (ref "JM2") (pin "92") (pinfunction "92_92") (pintype "bidirectional"))
    )
    (net (code "36") (name "B14_L20_N") (class "Default")
      (node (ref "JM2") (pin "95") (pinfunction "95_95") (pintype "bidirectional"))
      (node (ref "PCIE-SOUTH") (pin "B6") (pinfunction "IO2_B6") (pintype "passive"))
    )
    (net (code "37") (name "B14_L20_P") (class "Default")
      (node (ref "JM2") (pin "93") (pinfunction "93_93") (pintype "bidirectional"))
      (node (ref "PCIE-SOUTH") (pin "B7") (pinfunction "IO3_B7") (pintype "passive"))
    )
    (net (code "38") (name "B14_L21_N") (class "Default")
      (node (ref "JM1") (pin "95") (pinfunction "95_95") (pintype "bidirectional"))
      (node (ref "U5") (pin "1") (pinfunction "EN_1") (pintype "input"))
    )
    (net (code "39") (name "B14_L21_P") (class "Default")
      (node (ref "JM1") (pin "93") (pinfunction "93_93") (pintype "bidirectional"))
    )
    (net (code "40") (name "B14_L22_N") (class "Default")
      (node (ref "JM2") (pin "96") (pinfunction "96_96") (pintype "bidirectional"))
    )
    (net (code "41") (name "B14_L22_P") (class "Default")
      (node (ref "JM2") (pin "98") (pinfunction "98_98") (pintype "bidirectional"))
    )
    (net (code "42") (name "B14_L23_N") (class "Default")
      (node (ref "JM1") (pin "89") (pinfunction "89_89") (pintype "bidirectional"))
    )
    (net (code "43") (name "B14_L23_P") (class "Default")
      (node (ref "JM1") (pin "91") (pinfunction "91_91") (pintype "bidirectional"))
    )
    (net (code "44") (name "B14_L24_N") (class "Default")
      (node (ref "JM1") (pin "85") (pinfunction "85_85") (pintype "bidirectional"))
    )
    (net (code "45") (name "B14_L24_P") (class "Default")
      (node (ref "JM1") (pin "87") (pinfunction "87_87") (pintype "bidirectional"))
    )
    (net (code "46") (name "B14_L25") (class "Default")
      (node (ref "JM2") (pin "97") (pinfunction "97_97") (pintype "bidirectional"))
      (node (ref "PCIE-SOUTH") (pin "B5") (pinfunction "IO1_B5") (pintype "passive"))
    )
    (net (code "47") (name "B15_L1_N") (class "Default")
      (node (ref "JM2") (pin "14") (pinfunction "14_14") (pintype "bidirectional"))
      (node (ref "PCIE-NORTH") (pin "A14") (pinfunction "LVDS_3B_A14") (pintype "passive"))
    )
    (net (code "48") (name "B15_L1_P") (class "Default")
      (node (ref "JM2") (pin "16") (pinfunction "16_16") (pintype "bidirectional"))
      (node (ref "PCIE-NORTH") (pin "A13") (pinfunction "LVDS_3A_A13") (pintype "passive"))
    )
    (net (code "49") (name "B15_L2_N") (class "Default")
      (node (ref "JM2") (pin "20") (pinfunction "20_20") (pintype "bidirectional"))
    )
    (net (code "50") (name "B15_L2_P") (class "Default")
      (node (ref "JM2") (pin "22") (pinfunction "22_22") (pintype "bidirectional"))
    )
    (net (code "51") (name "B15_L3_N") (class "Default")
      (node (ref "JM2") (pin "4") (pinfunction "4_4") (pintype "bidirectional"))
    )
    (net (code "52") (name "B15_L3_P") (class "Default")
      (node (ref "JM2") (pin "2") (pinfunction "2_2") (pintype "bidirectional"))
    )
    (net (code "53") (name "B15_L4_N") (class "Default")
      (node (ref "JM2") (pin "10") (pinfunction "10_10") (pintype "bidirectional"))
    )
    (net (code "54") (name "B15_L4_P") (class "Default")
      (node (ref "JM2") (pin "12") (pinfunction "12_12") (pintype "bidirectional"))
    )
    (net (code "55") (name "B15_L5_N") (class "Default")
      (node (ref "JM2") (pin "8") (pinfunction "8_8") (pintype "bidirectional"))
      (node (ref "PCIE-NORTH") (pin "A16") (pinfunction "LVDS_4A_A16") (pintype "passive"))
    )
    (net (code "56") (name "B15_L5_P") (class "Default")
      (node (ref "JM2") (pin "6") (pinfunction "6_6") (pintype "bidirectional"))
      (node (ref "PCIE-NORTH") (pin "A17") (pinfunction "LVDS_4B_A17") (pintype "passive"))
    )
    (net (code "57") (name "B15_L6_N") (class "Default")
      (node (ref "JM2") (pin "26") (pinfunction "26_26") (pintype "bidirectional"))
      (node (ref "PCIE-NORTH") (pin "A5") (pinfunction "LVDS_1A_A5") (pintype "passive"))
    )
    (net (code "58") (name "B15_L6_P") (class "Default")
      (node (ref "JM2") (pin "24") (pinfunction "24_24") (pintype "bidirectional"))
      (node (ref "PCIE-NORTH") (pin "A6") (pinfunction "LVDS_1B_A6") (pintype "passive"))
    )
    (net (code "59") (name "B15_L7_N") (class "Default")
      (node (ref "JM2") (pin "1") (pinfunction "1_1") (pintype "bidirectional"))
      (node (ref "PCIE-NORTH") (pin "B17") (pinfunction "LVDS_5B_B17") (pintype "passive"))
    )
    (net (code "60") (name "B15_L7_P") (class "Default")
      (node (ref "JM2") (pin "3") (pinfunction "3_3") (pintype "bidirectional"))
      (node (ref "PCIE-NORTH") (pin "B16") (pinfunction "LVDS_5A_B16") (pintype "passive"))
    )
    (net (code "61") (name "B15_L8_N") (class "Default")
      (node (ref "JM2") (pin "7") (pinfunction "7_7") (pintype "bidirectional"))
    )
    (net (code "62") (name "B15_L8_P") (class "Default")
      (node (ref "JM2") (pin "5") (pinfunction "5_5") (pintype "bidirectional"))
    )
    (net (code "63") (name "B15_L9_N") (class "Default")
      (node (ref "JM2") (pin "15") (pinfunction "15_15") (pintype "bidirectional"))
    )
    (net (code "64") (name "B15_L9_P") (class "Default")
      (node (ref "JM2") (pin "13") (pinfunction "13_13") (pintype "bidirectional"))
    )
    (net (code "65") (name "B15_L10_N") (class "Default")
      (node (ref "JM2") (pin "11") (pinfunction "11_11") (pintype "bidirectional"))
      (node (ref "PCIE-NORTH") (pin "A8") (pinfunction "LVDS_2A_A8") (pintype "passive"))
    )
    (net (code "66") (name "B15_L10_P") (class "Default")
      (node (ref "JM2") (pin "9") (pinfunction "9_9") (pintype "bidirectional"))
      (node (ref "PCIE-NORTH") (pin "A9") (pinfunction "LVDS_2B_A9") (pintype "passive"))
    )
    (net (code "67") (name "B15_L11_N") (class "Default")
      (node (ref "JM2") (pin "30") (pinfunction "30_30") (pintype "bidirectional"))
    )
    (net (code "68") (name "B15_L11_P") (class "Default")
      (node (ref "JM2") (pin "28") (pinfunction "28_28") (pintype "bidirectional"))
    )
    (net (code "69") (name "B15_L12_N") (class "Default")
      (node (ref "JM2") (pin "34") (pinfunction "34_34") (pintype "bidirectional"))
      (node (ref "PCIE-SOUTH") (pin "A8") (pinfunction "LVDS_2A_A8") (pintype "passive"))
    )
    (net (code "70") (name "B15_L12_P") (class "Default")
      (node (ref "JM2") (pin "32") (pinfunction "32_32") (pintype "bidirectional"))
      (node (ref "PCIE-SOUTH") (pin "A9") (pinfunction "LVDS_2B_A9") (pintype "passive"))
    )
    (net (code "71") (name "B15_L13_N") (class "Default")
      (node (ref "JM2") (pin "38") (pinfunction "38_38") (pintype "bidirectional"))
      (node (ref "PCIE-SOUTH") (pin "A6") (pinfunction "LVDS_1B_A6") (pintype "passive"))
    )
    (net (code "72") (name "B15_L13_P") (class "Default")
      (node (ref "JM2") (pin "40") (pinfunction "40_40") (pintype "bidirectional"))
      (node (ref "PCIE-SOUTH") (pin "A5") (pinfunction "LVDS_1A_A5") (pintype "passive"))
    )
    (net (code "73") (name "B15_L14_N") (class "Default")
      (node (ref "JM2") (pin "42") (pinfunction "42_42") (pintype "bidirectional"))
    )
    (net (code "74") (name "B15_L14_P") (class "Default")
      (node (ref "JM2") (pin "44") (pinfunction "44_44") (pintype "bidirectional"))
    )
    (net (code "75") (name "B15_L15_N") (class "Default")
      (node (ref "JM2") (pin "19") (pinfunction "19_19") (pintype "bidirectional"))
      (node (ref "PCIE-NORTH") (pin "A3") (pinfunction "LVDS_0B_A3") (pintype "passive"))
    )
    (net (code "76") (name "B15_L15_P") (class "Default")
      (node (ref "JM2") (pin "21") (pinfunction "21_21") (pintype "bidirectional"))
      (node (ref "PCIE-NORTH") (pin "A2") (pinfunction "LVDS_0A_A2") (pintype "passive"))
    )
    (net (code "77") (name "B15_L16_N") (class "Default")
      (node (ref "JM2") (pin "23") (pinfunction "23_23") (pintype "bidirectional"))
    )
    (net (code "78") (name "B15_L16_P") (class "Default")
      (node (ref "JM2") (pin "25") (pinfunction "25_25") (pintype "bidirectional"))
    )
    (net (code "79") (name "B15_L17_N") (class "Default")
      (node (ref "JM2") (pin "31") (pinfunction "31_31") (pintype "bidirectional"))
    )
    (net (code "80") (name "B15_L17_P") (class "Default")
      (node (ref "JM2") (pin "33") (pinfunction "33_33") (pintype "bidirectional"))
    )
    (net (code "81") (name "B15_L18_N") (class "Default")
      (node (ref "JM2") (pin "27") (pinfunction "27_27") (pintype "bidirectional"))
      (node (ref "PCIE-SOUTH") (pin "A17") (pinfunction "LVDS_4B_A17") (pintype "passive"))
    )
    (net (code "82") (name "B15_L18_P") (class "Default")
      (node (ref "JM2") (pin "29") (pinfunction "29_29") (pintype "bidirectional"))
      (node (ref "PCIE-SOUTH") (pin "A16") (pinfunction "LVDS_4A_A16") (pintype "passive"))
    )
    (net (code "83") (name "B15_L19_N") (class "Default")
      (node (ref "JM2") (pin "41") (pinfunction "41_41") (pintype "bidirectional"))
      (node (ref "PCIE-SOUTH") (pin "B17") (pinfunction "LVDS_5B_B17") (pintype "passive"))
    )
    (net (code "84") (name "B15_L19_P") (class "Default")
      (node (ref "JM2") (pin "43") (pinfunction "43_43") (pintype "bidirectional"))
      (node (ref "PCIE-SOUTH") (pin "B16") (pinfunction "LVDS_5A_B16") (pintype "passive"))
    )
    (net (code "85") (name "B15_L20_N") (class "Default")
      (node (ref "JM2") (pin "50") (pinfunction "50_50") (pintype "bidirectional"))
    )
    (net (code "86") (name "B15_L20_P") (class "Default")
      (node (ref "JM2") (pin "52") (pinfunction "52_52") (pintype "bidirectional"))
    )
    (net (code "87") (name "B15_L21_N") (class "Default")
      (node (ref "JM2") (pin "45") (pinfunction "45_45") (pintype "bidirectional"))
    )
    (net (code "88") (name "B15_L21_P") (class "Default")
      (node (ref "JM2") (pin "47") (pinfunction "47_47") (pintype "bidirectional"))
    )
    (net (code "89") (name "B15_L22_N") (class "Default")
      (node (ref "JM2") (pin "46") (pinfunction "46_46") (pintype "bidirectional"))
      (node (ref "PCIE-SOUTH") (pin "A3") (pinfunction "LVDS_0B_A3") (pintype "passive"))
    )
    (net (code "90") (name "B15_L22_P") (class "Default")
      (node (ref "JM2") (pin "48") (pinfunction "48_48") (pintype "bidirectional"))
      (node (ref "PCIE-SOUTH") (pin "A2") (pinfunction "LVDS_0A_A2") (pintype "passive"))
    )
    (net (code "91") (name "B15_L23_N") (class "Default")
      (node (ref "JM2") (pin "51") (pinfunction "51_51") (pintype "bidirectional"))
      (node (ref "PCIE-SOUTH") (pin "A13") (pinfunction "LVDS_3A_A13") (pintype "passive"))
    )
    (net (code "92") (name "B15_L23_P") (class "Default")
      (node (ref "JM2") (pin "49") (pinfunction "49_49") (pintype "bidirectional"))
      (node (ref "PCIE-SOUTH") (pin "A14") (pinfunction "LVDS_3B_A14") (pintype "passive"))
    )
    (net (code "93") (name "B15_L24_N") (class "Default")
      (node (ref "JM2") (pin "37") (pinfunction "37_37") (pintype "bidirectional"))
    )
    (net (code "94") (name "B15_L24_P") (class "Default")
      (node (ref "JM2") (pin "39") (pinfunction "39_39") (pintype "bidirectional"))
    )
    (net (code "95") (name "B34_L1_N") (class "Default")
      (node (ref "JM1") (pin "37") (pinfunction "37_37") (pintype "bidirectional"))
    )
    (net (code "96") (name "B34_L1_P") (class "Default")
      (node (ref "JM1") (pin "35") (pinfunction "35_35") (pintype "bidirectional"))
    )
    (net (code "97") (name "B34_L2_N") (class "Default")
      (node (ref "JM1") (pin "33") (pinfunction "33_33") (pintype "bidirectional"))
    )
    (net (code "98") (name "B34_L2_P") (class "Default")
      (node (ref "JM1") (pin "31") (pinfunction "31_31") (pintype "bidirectional"))
    )
    (net (code "99") (name "B34_L3_N") (class "Default")
      (node (ref "JM1") (pin "42") (pinfunction "42_42") (pintype "bidirectional"))
      (node (ref "U3") (pin "13") (pinfunction "SCLK_13") (pintype "input"))
    )
    (net (code "100") (name "B34_L3_P") (class "Default")
      (node (ref "JM1") (pin "40") (pinfunction "40_40") (pintype "bidirectional"))
      (node (ref "U3") (pin "17") (pinfunction "GPIO0_17") (pintype "bidirectional"))
    )
    (net (code "101") (name "B34_L4_N") (class "Default")
      (node (ref "JM1") (pin "41") (pinfunction "41_41") (pintype "bidirectional"))
      (node (ref "U3") (pin "12") (pinfunction "SDOUT_12") (pintype "output"))
    )
    (net (code "102") (name "B34_L4_P") (class "Default")
      (node (ref "JM1") (pin "39") (pinfunction "39_39") (pintype "bidirectional"))
    )
    (net (code "103") (name "B34_L5_N") (class "Default")
      (node (ref "JM1") (pin "45") (pinfunction "45_45") (pintype "bidirectional"))
      (node (ref "U3") (pin "10") (pinfunction "~{CS}_10") (pintype "input"))
    )
    (net (code "104") (name "B34_L5_P") (class "Default")
      (node (ref "JM1") (pin "43") (pinfunction "43_43") (pintype "bidirectional"))
      (node (ref "U3") (pin "11") (pinfunction "SDIN_11") (pintype "input"))
    )
    (net (code "105") (name "B34_L6_N") (class "Default")
      (node (ref "JM1") (pin "34") (pinfunction "34_34") (pintype "bidirectional"))
    )
    (net (code "106") (name "B34_L6_P") (class "Default")
      (node (ref "JM1") (pin "32") (pinfunction "32_32") (pintype "bidirectional"))
    )
    (net (code "107") (name "B34_L7_N") (class "Default")
      (node (ref "JM1") (pin "38") (pinfunction "38_38") (pintype "bidirectional"))
      (node (ref "U3") (pin "18") (pinfunction "GPIO1_18") (pintype "bidirectional"))
    )
    (net (code "108") (name "B34_L7_P") (class "Default")
      (node (ref "JM1") (pin "36") (pinfunction "36_36") (pintype "bidirectional"))
    )
    (net (code "109") (name "B34_L8_N") (class "Default")
      (node (ref "JM1") (pin "52") (pinfunction "52_52") (pintype "bidirectional"))
      (node (ref "U2") (pin "13") (pinfunction "SCLK_13") (pintype "input"))
    )
    (net (code "110") (name "B34_L8_P") (class "Default")
      (node (ref "JM1") (pin "50") (pinfunction "50_50") (pintype "bidirectional"))
      (node (ref "U2") (pin "12") (pinfunction "SDOUT_12") (pintype "output"))
    )
    (net (code "111") (name "B34_L9_N") (class "Default")
      (node (ref "JM1") (pin "46") (pinfunction "46_46") (pintype "bidirectional"))
      (node (ref "U3") (pin "33") (pinfunction "GPIO2_33") (pintype "bidirectional"))
    )
    (net (code "112") (name "B34_L9_P") (class "Default")
      (node (ref "JM1") (pin "44") (pinfunction "44_44") (pintype "bidirectional"))
      (node (ref "U3") (pin "36") (pinfunction "GPIO3_36") (pintype "bidirectional"))
    )
    (net (code "113") (name "B34_L10_N") (class "Default")
      (node (ref "JM1") (pin "51") (pinfunction "51_51") (pintype "bidirectional"))
      (node (ref "U4") (pin "11") (pinfunction "SDIN_11") (pintype "input"))
    )
    (net (code "114") (name "B34_L10_P") (class "Default")
      (node (ref "JM1") (pin "49") (pinfunction "49_49") (pintype "bidirectional"))
      (node (ref "U4") (pin "10") (pinfunction "~{CS}_10") (pintype "input"))
    )
    (net (code "115") (name "B34_L11_N") (class "Default")
      (node (ref "JM1") (pin "53") (pinfunction "53_53") (pintype "bidirectional"))
      (node (ref "U4") (pin "12") (pinfunction "SDOUT_12") (pintype "output"))
    )
    (net (code "116") (name "B34_L11_P") (class "Default")
      (node (ref "JM1") (pin "55") (pinfunction "55_55") (pintype "bidirectional"))
      (node (ref "U4") (pin "17") (pinfunction "GPIO0_17") (pintype "bidirectional"))
    )
    (net (code "117") (name "B34_L12_N") (class "Default")
      (node (ref "JM1") (pin "57") (pinfunction "57_57") (pintype "bidirectional"))
      (node (ref "U4") (pin "18") (pinfunction "GPIO1_18") (pintype "bidirectional"))
    )
    (net (code "118") (name "B34_L12_P") (class "Default")
      (node (ref "JM1") (pin "59") (pinfunction "59_59") (pintype "bidirectional"))
      (node (ref "U2") (pin "11") (pinfunction "SDIN_11") (pintype "input"))
    )
    (net (code "119") (name "B34_L13_N") (class "Default")
      (node (ref "JM1") (pin "56") (pinfunction "56_56") (pintype "bidirectional"))
      (node (ref "U2") (pin "18") (pinfunction "GPIO1_18") (pintype "bidirectional"))
    )
    (net (code "120") (name "B34_L13_P") (class "Default")
      (node (ref "JM1") (pin "54") (pinfunction "54_54") (pintype "bidirectional"))
      (node (ref "U2") (pin "17") (pinfunction "GPIO0_17") (pintype "bidirectional"))
    )
    (net (code "121") (name "B34_L14_N") (class "Default")
      (node (ref "JM1") (pin "60") (pinfunction "60_60") (pintype "bidirectional"))
      (node (ref "U2") (pin "36") (pinfunction "GPIO3_36") (pintype "bidirectional"))
    )
    (net (code "122") (name "B34_L14_P") (class "Default")
      (node (ref "JM1") (pin "58") (pinfunction "58_58") (pintype "bidirectional"))
      (node (ref "U2") (pin "33") (pinfunction "GPIO2_33") (pintype "bidirectional"))
    )
    (net (code "123") (name "B34_L15_N") (class "Default")
      (node (ref "JM1") (pin "62") (pinfunction "62_62") (pintype "bidirectional"))
    )
    (net (code "124") (name "B34_L15_P") (class "Default")
      (node (ref "JM1") (pin "64") (pinfunction "64_64") (pintype "bidirectional"))
    )
    (net (code "125") (name "B34_L16_N") (class "Default")
      (node (ref "JM1") (pin "68") (pinfunction "68_68") (pintype "bidirectional"))
    )
    (net (code "126") (name "B34_L16_P") (class "Default")
      (node (ref "JM1") (pin "70") (pinfunction "70_70") (pintype "bidirectional"))
    )
    (net (code "127") (name "B34_L17_N") (class "Default")
      (node (ref "JM1") (pin "63") (pinfunction "63_63") (pintype "bidirectional"))
      (node (ref "U2") (pin "10") (pinfunction "~{CS}_10") (pintype "input"))
    )
    (net (code "128") (name "B34_L17_P") (class "Default")
      (node (ref "JM1") (pin "65") (pinfunction "65_65") (pintype "bidirectional"))
      (node (ref "U4") (pin "36") (pinfunction "GPIO3_36") (pintype "bidirectional"))
    )
    (net (code "129") (name "B34_L18_N") (class "Default")
      (node (ref "JM1") (pin "74") (pinfunction "74_74") (pintype "bidirectional"))
    )
    (net (code "130") (name "B34_L18_P") (class "Default")
      (node (ref "JM1") (pin "72") (pinfunction "72_72") (pintype "bidirectional"))
    )
    (net (code "131") (name "B34_L19_N") (class "Default")
      (node (ref "JM1") (pin "71") (pinfunction "71_71") (pintype "bidirectional"))
    )
    (net (code "132") (name "B34_L19_P") (class "Default")
      (node (ref "JM1") (pin "73") (pinfunction "73_73") (pintype "bidirectional"))
    )
    (net (code "133") (name "B34_L20_N") (class "Default")
      (node (ref "JM1") (pin "76") (pinfunction "76_76") (pintype "bidirectional"))
      (node (ref "R4") (pin "1") (pinfunction "1_1") (pintype "passive"))
    )
    (net (code "134") (name "B34_L20_P") (class "Default")
      (node (ref "JM1") (pin "78") (pinfunction "78_78") (pintype "bidirectional"))
      (node (ref "R5") (pin "1") (pinfunction "1_1") (pintype "passive"))
    )
    (net (code "135") (name "B34_L21_N") (class "Default")
      (node (ref "JM1") (pin "69") (pinfunction "69_69") (pintype "bidirectional"))
    )
    (net (code "136") (name "B34_L21_P") (class "Default")
      (node (ref "JM1") (pin "67") (pinfunction "67_67") (pintype "bidirectional"))
      (node (ref "U4") (pin "33") (pinfunction "GPIO2_33") (pintype "bidirectional"))
    )
    (net (code "137") (name "B34_L22_N") (class "Default")
      (node (ref "JM1") (pin "75") (pinfunction "75_75") (pintype "bidirectional"))
    )
    (net (code "138") (name "B34_L22_P") (class "Default")
      (node (ref "JM1") (pin "77") (pinfunction "77_77") (pintype "bidirectional"))
    )
    (net (code "139") (name "B34_L23_N") (class "Default")
      (node (ref "JM1") (pin "79") (pinfunction "79_79") (pintype "bidirectional"))
    )
    (net (code "140") (name "B34_L23_P") (class "Default")
      (node (ref "JM1") (pin "81") (pinfunction "81_81") (pintype "bidirectional"))
    )
    (net (code "141") (name "B34_L24_N") (class "Default")
      (node (ref "JM1") (pin "80") (pinfunction "80_80") (pintype "bidirectional"))
      (node (ref "R6") (pin "1") (pinfunction "1_1") (pintype "passive"))
    )
    (net (code "142") (name "B34_L24_P") (class "Default")
      (node (ref "JM1") (pin "82") (pinfunction "82_82") (pintype "bidirectional"))
      (node (ref "R7") (pin "1") (pinfunction "1_1") (pintype "passive"))
    )
    (net (code "143") (name "BOOTMODE") (class "Default")
      (node (ref "JM2") (pin "100") (pinfunction "100_100") (pintype "bidirectional"))
      (node (ref "JP3") (pin "1") (pinfunction "1_1") (pintype "passive"))
    )
    (net (code "144") (name "DONE") (class "Default")
      (node (ref "D5") (pin "A") (pinfunction "A_A") (pintype "passive"))
      (node (ref "JM1") (pin "96") (pinfunction "96_96") (pintype "bidirectional"))
      (node (ref "R3") (pin "1") (pinfunction "1_1") (pintype "passive"))
    )
    (net (code "145") (name "EN_A") (class "Default")
      (node (ref "U6") (pin "1") (pinfunction "EN_1") (pintype "input"))
    )
    (net (code "146") (name "EN_B") (class "Default")
      (node (ref "U9") (pin "1") (pinfunction "EN_1") (pintype "input"))
    )
    (net (code "147") (name "FB_A") (class "Default")
      (node (ref "R17") (pin "2") (pinfunction "2_2") (pintype "passive"))
      (node (ref "R18") (pin "1") (pinfunction "1_1") (pintype "passive"))
      (node (ref "U6") (pin "7") (pinfunction "FB_7") (pintype "output"))
    )
    (net (code "148") (name "FB_B") (class "Default")
      (node (ref "R16") (pin "1") (pinfunction "1_1") (pintype "passive"))
      (node (ref "R19") (pin "2") (pinfunction "2_2") (pintype "passive"))
      (node (ref "U9") (pin "7") (pinfunction "FB_7") (pintype "output"))
    )
    (net (code "149") (name "GND") (class "Default")
      (node (ref "C1") (pin "2") (pinfunction "2_2") (pintype "passive"))
      (node (ref "C10") (pin "2") (pinfunction "2_2") (pintype "passive"))
      (node (ref "C11") (pin "2") (pinfunction "2_2") (pintype "passive"))
      (node (ref "C12") (pin "2") (pinfunction "2_2") (pintype "passive"))
      (node (ref "C13") (pin "2") (pinfunction "2_2") (pintype "passive"))
      (node (ref "C14") (pin "2") (pinfunction "2_2") (pintype "passive"))
      (node (ref "C15") (pin "2") (pinfunction "2_2") (pintype "passive"))
      (node (ref "C16") (pin "2") (pinfunction "2_2") (pintype "passive"))
      (node (ref "C22") (pin "2") (pinfunction "2_2") (pintype "passive"))
      (node (ref "C23") (pin "2") (pinfunction "2_2") (pintype "passive"))
      (node (ref "C24") (pin "2") (pinfunction "2_2") (pintype "passive"))
      (node (ref "C25") (pin "2") (pinfunction "2_2") (pintype "passive"))
      (node (ref "C26") (pin "2") (pinfunction "2_2") (pintype "passive"))
      (node (ref "C27") (pin "2") (pinfunction "2_2") (pintype "passive"))
      (node (ref "C28") (pin "2") (pinfunction "2_2") (pintype "passive"))
      (node (ref "C29") (pin "2") (pinfunction "2_2") (pintype "passive"))
      (node (ref "C30") (pin "2") (pinfunction "2_2") (pintype "passive"))
      (node (ref "C31") (pin "2") (pinfunction "2_2") (pintype "passive"))
      (node (ref "C32") (pin "2") (pinfunction "2_2") (pintype "passive"))
      (node (ref "C33") (pin "2") (pinfunction "2_2") (pintype "passive"))
      (node (ref "C34") (pin "2") (pinfunction "2_2") (pintype "passive"))
      (node (ref "C40") (pin "2") (pinfunction "2_2") (pintype "passive"))
      (node (ref "C41") (pin "2") (pinfunction "2_2") (pintype "passive"))
      (node (ref "C42") (pin "2") (pinfunction "2_2") (pintype "passive"))
      (node (ref "C43") (pin "2") (pinfunction "2_2") (pintype "passive"))
      (node (ref "C44") (pin "2") (pinfunction "2_2") (pintype "passive"))
      (node (ref "C45") (pin "2") (pinfunction "2_2") (pintype "passive"))
      (node (ref "C46") (pin "2") (pinfunction "2_2") (pintype "passive"))
      (node (ref "C47") (pin "2") (pinfunction "2_2") (pintype "passive"))
      (node (ref "C48") (pin "2") (pinfunction "2_2") (pintype "passive"))
      (node (ref "C49") (pin "2") (pinfunction "2_2") (pintype "passive"))
      (node (ref "C5") (pin "2") (pinfunction "2_2") (pintype "passive"))
      (node (ref "C50") (pin "2") (pinfunction "2_2") (pintype "passive"))
      (node (ref "C51") (pin "2") (pinfunction "2_2") (pintype "passive"))
      (node (ref "C52") (pin "2") (pinfunction "2_2") (pintype "passive"))
      (node (ref "C53") (pin "2") (pinfunction "2_2") (pintype "passive"))
      (node (ref "C56") (pin "2") (pinfunction "2_2") (pintype "passive"))
      (node (ref "C57") (pin "2") (pinfunction "2_2") (pintype "passive"))
      (node (ref "C58") (pin "2") (pinfunction "2_2") (pintype "passive"))
      (node (ref "C59") (pin "2") (pinfunction "2_2") (pintype "passive"))
      (node (ref "C6") (pin "2") (pinfunction "2_2") (pintype "passive"))
      (node (ref "C7") (pin "2") (pinfunction "2_2") (pintype "passive"))
      (node (ref "C8") (pin "2") (pinfunction "2_2") (pintype "passive"))
      (node (ref "C9") (pin "2") (pinfunction "2_2") (pintype "passive"))
      (node (ref "D5") (pin "C") (pinfunction "C_C") (pintype "passive"))
      (node (ref "JM1") (pin "100") (pinfunction "100_100") (pintype "bidirectional"))
      (node (ref "JM1") (pin "11") (pinfunction "11_11") (pintype "bidirectional"))
      (node (ref "JM1") (pin "12") (pinfunction "12_12") (pintype "bidirectional"))
      (node (ref "JM1") (pin "17") (pinfunction "17_17") (pintype "bidirectional"))
      (node (ref "JM1") (pin "18") (pinfunction "18_18") (pintype "bidirectional"))
      (node (ref "JM1") (pin "23") (pinfunction "23_23") (pintype "bidirectional"))
      (node (ref "JM1") (pin "24") (pinfunction "24_24") (pintype "bidirectional"))
      (node (ref "JM1") (pin "29") (pinfunction "29_29") (pintype "bidirectional"))
      (node (ref "JM1") (pin "30") (pinfunction "30_30") (pintype "bidirectional"))
      (node (ref "JM1") (pin "47") (pinfunction "47_47") (pintype "bidirectional"))
      (node (ref "JM1") (pin "48") (pinfunction "48_48") (pintype "bidirectional"))
      (node (ref "JM1") (pin "5") (pinfunction "5_5") (pintype "bidirectional"))
      (node (ref "JM1") (pin "6") (pinfunction "6_6") (pintype "bidirectional"))
      (node (ref "JM1") (pin "66") (pinfunction "66_66") (pintype "bidirectional"))
      (node (ref "JM1") (pin "84") (pinfunction "84_84") (pintype "bidirectional"))
      (node (ref "JM1") (pin "98") (pinfunction "98_98") (pintype "bidirectional"))
      (node (ref "JM1") (pin "F1") (pinfunction "F1_F1") (pintype "bidirectional"))
      (node (ref "JM1") (pin "F2") (pinfunction "F2_F2") (pintype "bidirectional"))
      (node (ref "JM2") (pin "17") (pinfunction "17_17") (pintype "bidirectional"))
      (node (ref "JM2") (pin "35") (pinfunction "35_35") (pintype "bidirectional"))
      (node (ref "JM2") (pin "36") (pinfunction "36_36") (pintype "bidirectional"))
      (node (ref "JM2") (pin "72") (pinfunction "72_72") (pintype "bidirectional"))
      (node (ref "JM2") (pin "83") (pinfunction "83_83") (pintype "bidirectional"))
      (node (ref "JM2") (pin "90") (pinfunction "90_90") (pintype "bidirectional"))
      (node (ref "JM2") (pin "F1") (pinfunction "F1_F1") (pintype "bidirectional"))
      (node (ref "JM2") (pin "F2") (pinfunction "F2_F2") (pintype "bidirectional"))
      (node (ref "JP1") (pin "1") (pinfunction "1_1") (pintype "passive"))
      (node (ref "JP1") (pin "11") (pinfunction "11_11") (pintype "passive"))
      (node (ref "JP1") (pin "13") (pinfunction "13_13") (pintype "passive"))
      (node (ref "JP1") (pin "3") (pinfunction "3_3") (pintype "passive"))
      (node (ref "JP1") (pin "5") (pinfunction "5_5") (pintype "passive"))
      (node (ref "JP1") (pin "7") (pinfunction "7_7") (pintype "passive"))
      (node (ref "JP1") (pin "9") (pinfunction "9_9") (pintype "passive"))
      (node (ref "JP2") (pin "3") (pinfunction "3_3") (pintype "passive"))
      (node (ref "JP3") (pin "2") (pinfunction "2_2") (pintype "passive"))
      (node (ref "PCIE-NORTH") (pin "A1") (pinfunction "GND_A1") (pintype "passive"))
      (node (ref "PCIE-NORTH") (pin "A10") (pinfunction "GND_A10") (pintype "passive"))
      (node (ref "PCIE-NORTH") (pin "A12") (pinfunction "GND_A12") (pintype "passive"))
      (node (ref "PCIE-NORTH") (pin "A15") (pinfunction "GND_A15") (pintype "passive"))
      (node (ref "PCIE-NORTH") (pin "A18") (pinfunction "GND_A18") (pintype "passive"))
      (node (ref "PCIE-NORTH") (pin "A4") (pinfunction "GND_A4") (pintype "passive"))
      (node (ref "PCIE-NORTH") (pin "A7") (pinfunction "GND_A7") (pintype "passive"))
      (node (ref "PCIE-NORTH") (pin "B15") (pinfunction "GND_B15") (pintype "passive"))
      (node (ref "PCIE-NORTH") (pin "B18") (pinfunction "GND_B18") (pintype "passive"))
      (node (ref "PCIE-SOUTH") (pin "A1") (pinfunction "GND_A1") (pintype "passive"))
      (node (ref "PCIE-SOUTH") (pin "A10") (pinfunction "GND_A10") (pintype "passive"))
      (node (ref "PCIE-SOUTH") (pin "A12") (pinfunction "GND_A12") (pintype "passive"))
      (node (ref "PCIE-SOUTH") (pin "A15") (pinfunction "GND_A15") (pintype "passive"))
      (node (ref "PCIE-SOUTH") (pin "A18") (pinfunction "GND_A18") (pintype "passive"))
      (node (ref "PCIE-SOUTH") (pin "A4") (pinfunction "GND_A4") (pintype "passive"))
      (node (ref "PCIE-SOUTH") (pin "A7") (pinfunction "GND_A7") (pintype "passive"))
      (node (ref "PCIE-SOUTH") (pin "B15") (pinfunction "GND_B15") (pintype "passive"))
      (node (ref "PCIE-SOUTH") (pin "B18") (pinfunction "GND_B18") (pintype "passive"))
      (node (ref "R10") (pin "2") (pinfunction "2_2") (pintype "passive"))
      (node (ref "R11") (pin "2") (pinfunction "2_2") (pintype "passive"))
      (node (ref "R12") (pin "2") (pinfunction "2_2") (pintype "passive"))
      (node (ref "R13") (pin "2") (pinfunction "2_2") (pintype "passive"))
      (node (ref "R14") (pin "2") (pinfunction "2_2") (pintype "passive"))
      (node (ref "R17") (pin "1") (pinfunction "1_1") (pintype "passive"))
      (node (ref "R19") (pin "1") (pinfunction "1_1") (pintype "passive"))
      (node (ref "R2") (pin "2") (pinfunction "2_2") (pintype "passive"))
      (node (ref "R8") (pin "2") (pinfunction "2_2") (pintype "passive"))
      (node (ref "R9") (pin "2") (pinfunction "2_2") (pintype "passive"))
      (node (ref "U1") (pin "1") (pinfunction "A0_1") (pintype "input"))
      (node (ref "U1") (pin "2") (pinfunction "A1_2") (pintype "input"))
      (node (ref "U1") (pin "3") (pinfunction "A2_3") (pintype "input"))
      (node (ref "U1") (pin "4") (pinfunction "GND_4") (pintype "passive"))
      (node (ref "U1") (pin "EP") (pinfunction "EP_EP") (pintype "passive"))
      (node (ref "U2") (pin "1") (pinfunction "VEE_SDI_1") (pintype "power_in"))
      (node (ref "U2") (pin "14") (pinfunction "VSS_14") (pintype "power_in"))
      (node (ref "U2") (pin "15") (pinfunction "VSS_15") (pintype "power_in"))
      (node (ref "U2") (pin "19") (pinfunction "VEE_CORE_19") (pintype "power_in"))
      (node (ref "U2") (pin "21") (pinfunction "VEEO_21") (pintype "power_in"))
      (node (ref "U2") (pin "28") (pinfunction "VEEO_28") (pintype "power_in"))
      (node (ref "U2") (pin "31") (pinfunction "VEE_CORE_31") (pintype "power_in"))
      (node (ref "U2") (pin "37") (pinfunction "VEE_CORE_37") (pintype "power_in"))
      (node (ref "U2") (pin "38") (pinfunction "VEE_CORE_38") (pintype "power_in"))
      (node (ref "U2") (pin "8") (pinfunction "VEE_SDI_8") (pintype "power_in"))
      (node (ref "U3") (pin "1") (pinfunction "VEE_DDI_1") (pintype "power_in"))
      (node (ref "U3") (pin "14") (pinfunction "VSS_14") (pintype "power_in"))
      (node (ref "U3") (pin "15") (pinfunction "VSS_15") (pintype "power_in"))
      (node (ref "U3") (pin "19") (pinfunction "VEE_CORE_19") (pintype "power_in"))
      (node (ref "U3") (pin "21") (pinfunction "VEEO_21") (pintype "power_in"))
      (node (ref "U3") (pin "28") (pinfunction "VEEO_28") (pintype "power_in"))
      (node (ref "U3") (pin "31") (pinfunction "VEE_CORE_31") (pintype "power_in"))
      (node (ref "U3") (pin "37") (pinfunction "VEE_CORE_37") (pintype "power_in"))
      (node (ref "U3") (pin "38") (pinfunction "VEE_CORE_38") (pintype "power_in"))
      (node (ref "U3") (pin "8") (pinfunction "VEE_DDI_8") (pintype "power_in"))
      (node (ref "U4") (pin "1") (pinfunction "VEE_DDI_1") (pintype "power_in"))
      (node (ref "U4") (pin "14") (pinfunction "VSS_14") (pintype "power_in"))
      (node (ref "U4") (pin "15") (pinfunction "VSS_15") (pintype "power_in"))
      (node (ref "U4") (pin "19") (pinfunction "VEE_CORE_19") (pintype "power_in"))
      (node (ref "U4") (pin "21") (pinfunction "VEEO_21") (pintype "power_in"))
      (node (ref "U4") (pin "28") (pinfunction "VEEO_28") (pintype "power_in"))
      (node (ref "U4") (pin "31") (pinfunction "VEE_CORE_31") (pintype "power_in"))
      (node (ref "U4") (pin "37") (pinfunction "VEE_CORE_37") (pintype "power_in"))
      (node (ref "U4") (pin "38") (pinfunction "VEE_CORE_38") (pintype "power_in"))
      (node (ref "U4") (pin "8") (pinfunction "VEE_DDI_8") (pintype "power_in"))
      (node (ref "U5") (pin "3") (pinfunction "GND_3") (pintype "passive"))
      (node (ref "U6") (pin "5") (pinfunction "GND_5") (pintype "passive"))
      (node (ref "U6") (pin "6") (pinfunction "GND_6") (pintype "passive"))
      (node (ref "U6") (pin "EP") (pinfunction "GND_EP") (pintype "passive"))
      (node (ref "U9") (pin "5") (pinfunction "GND_5") (pintype "passive"))
      (node (ref "U9") (pin "6") (pinfunction "GND_6") (pintype "passive"))
      (node (ref "U9") (pin "EP") (pinfunction "GND_EP") (pintype "passive"))
      (node (ref "X1") (pin "2@1") (pinfunction "GND_2@1") (pintype "passive"))
      (node (ref "X1") (pin "2@2") (pinfunction "GND_2@2") (pintype "passive"))
      (node (ref "X1") (pin "2@3") (pinfunction "GND_2@3") (pintype "passive"))
      (node (ref "X2") (pin "2@1") (pinfunction "GND_2@1") (pintype "passive"))
      (node (ref "X2") (pin "2@2") (pinfunction "GND_2@2") (pintype "passive"))
      (node (ref "X2") (pin "2@3") (pinfunction "GND_2@3") (pintype "passive"))
      (node (ref "X3") (pin "2@1") (pinfunction "GND_2@1") (pintype "passive"))
      (node (ref "X3") (pin "2@2") (pinfunction "GND_2@2") (pintype "passive"))
      (node (ref "X3") (pin "2@3") (pinfunction "GND_2@3") (pintype "passive"))
    )
    (net (code "150") (name "I2C_V") (class "Default")
      (node (ref "C1") (pin "1") (pinfunction "1_1") (pintype "passive"))
      (node (ref "PCIE-NORTH") (pin "B3") (pinfunction "V_I2C_B3") (pintype "passive"))
      (node (ref "R1") (pin "1") (pinfunction "1_1") (pintype "passive"))
      (node (ref "U1") (pin "8") (pinfunction "VCC_8") (pintype "power_in"))
    )
    (net (code "151") (name "MGT_CLK0_N") (class "Default")
      (node (ref "C55") (pin "2") (pinfunction "2_2") (pintype "passive"))
      (node (ref "JM1") (pin "4") (pinfunction "4_4") (pintype "bidirectional"))
    )
    (net (code "152") (name "MGT_CLK0_P") (class "Default")
      (node (ref "C54") (pin "2") (pinfunction "2_2") (pintype "passive"))
      (node (ref "JM1") (pin "2") (pinfunction "2_2") (pintype "bidirectional"))
    )
    (net (code "153") (name "MGT_RX0_N") (class "Default")
      (node (ref "JM1") (pin "21") (pinfunction "21_21") (pintype "bidirectional"))
      (node (ref "U2") (pin "27") (pinfunction "DDO0_27") (pintype "output"))
    )
    (net (code "154") (name "MGT_RX0_P") (class "Default")
      (node (ref "JM1") (pin "19") (pinfunction "19_19") (pintype "bidirectional"))
      (node (ref "U2") (pin "26") (pinfunction "~{DDO0}_26") (pintype "output"))
    )
    (net (code "155") (name "MGT_RX1_N") (class "Default")
      (node (ref "JM1") (pin "15") (pinfunction "15_15") (pintype "bidirectional"))
      (node (ref "U2") (pin "23") (pinfunction "DDO1/RCO_23") (pintype "output"))
    )
    (net (code "156") (name "MGT_RX1_P") (class "Default")
      (node (ref "JM1") (pin "13") (pinfunction "13_13") (pintype "bidirectional"))
      (node (ref "U2") (pin "22") (pinfunction "~{DDO1}/~{RCO}_22") (pintype "output"))
    )
    (net (code "157") (name "MGT_RX2_N") (class "Default")
      (node (ref "JM1") (pin "9") (pinfunction "9_9") (pintype "bidirectional"))
    )
    (net (code "158") (name "MGT_RX2_P") (class "Default")
      (node (ref "JM1") (pin "7") (pinfunction "7_7") (pintype "bidirectional"))
    )
    (net (code "159") (name "MGT_RX3_N") (class "Default")
      (node (ref "JM1") (pin "3") (pinfunction "3_3") (pintype "bidirectional"))
    )
    (net (code "160") (name "MGT_RX3_P") (class "Default")
      (node (ref "JM1") (pin "1") (pinfunction "1_1") (pintype "bidirectional"))
    )
    (net (code "161") (name "MGT_TX0_N") (class "Default")
      (node (ref "JM1") (pin "28") (pinfunction "28_28") (pintype "bidirectional"))
      (node (ref "U4") (pin "6") (pinfunction "DDI_6") (pintype "input"))
    )
    (net (code "162") (name "MGT_TX0_P") (class "Default")
      (node (ref "JM1") (pin "26") (pinfunction "26_26") (pintype "bidirectional"))
      (node (ref "U4") (pin "7") (pinfunction "~{DDI}_7") (pintype "input"))
    )
    (net (code "163") (name "MGT_TX1_N") (class "Default")
      (node (ref "JM1") (pin "22") (pinfunction "22_22") (pintype "bidirectional"))
      (node (ref "U3") (pin "6") (pinfunction "DDI_6") (pintype "input"))
    )
    (net (code "164") (name "MGT_TX1_P") (class "Default")
      (node (ref "JM1") (pin "20") (pinfunction "20_20") (pintype "bidirectional"))
      (node (ref "U3") (pin "7") (pinfunction "~{DDI}_7") (pintype "input"))
    )
    (net (code "165") (name "MGT_TX2_N") (class "Default")
      (node (ref "JM1") (pin "16") (pinfunction "16_16") (pintype "bidirectional"))
    )
    (net (code "166") (name "MGT_TX2_P") (class "Default")
      (node (ref "JM1") (pin "14") (pinfunction "14_14") (pintype "bidirectional"))
    )
    (net (code "167") (name "MGT_TX3_N") (class "Default")
      (node (ref "JM1") (pin "10") (pinfunction "10_10") (pintype "bidirectional"))
    )
    (net (code "168") (name "MGT_TX3_P") (class "Default")
      (node (ref "JM1") (pin "8") (pinfunction "8_8") (pintype "bidirectional"))
    )
    (net (code "169") (name "N$34") (class "Default")
      (node (ref "U3") (pin "32") (pinfunction "RCLK_32") (pintype "input"))
    )
    (net (code "170") (name "N$81") (class "Default")
      (node (ref "U4") (pin "32") (pinfunction "RCLK_32") (pintype "input"))
    )
    (net (code "171") (name "N$83") (class "Default")
      (node (ref "U4") (pin "13") (pinfunction "SCLK_13") (pintype "input"))
    )
    (net (code "172") (name "N_5V") (class "Default")
      (node (ref "PCIE-NORTH") (pin "B12") (pinfunction "5V_B12") (pintype "passive"))
    )
    (net (code "173") (name "N_IO0") (class "Default")
      (node (ref "PCIE-NORTH") (pin "B4") (pinfunction "IO0_B4") (pintype "passive"))
    )
    (net (code "174") (name "N_IO1") (class "Default")
      (node (ref "PCIE-NORTH") (pin "B5") (pinfunction "IO1_B5") (pintype "passive"))
    )
    (net (code "175") (name "N_IO2") (class "Default")
      (node (ref "PCIE-NORTH") (pin "B6") (pinfunction "IO2_B6") (pintype "passive"))
    )
    (net (code "176") (name "N_IO3") (class "Default")
      (node (ref "PCIE-NORTH") (pin "B7") (pinfunction "IO3_B7") (pintype "passive"))
    )
    (net (code "177") (name "N_IO4") (class "Default")
      (node (ref "PCIE-NORTH") (pin "B8") (pinfunction "IO4_B8") (pintype "passive"))
    )
    (net (code "178") (name "N_IO5") (class "Default")
      (node (ref "PCIE-NORTH") (pin "B9") (pinfunction "IO5_B9") (pintype "passive"))
    )
    (net (code "179") (name "N_IO6") (class "Default")
      (node (ref "PCIE-NORTH") (pin "B10") (pinfunction "IO6_B10") (pintype "passive"))
    )
    (net (code "180") (name "N_IO7") (class "Default")
      (node (ref "PCIE-NORTH") (pin "B11") (pinfunction "IO7_B11") (pintype "passive"))
    )
    (net (code "181") (name "N_PCIE_V") (class "Default")
      (node (ref "PCIE-NORTH") (pin "B13") (pinfunction "VCC_B13") (pintype "passive"))
    )
    (net (code "182") (name "N_VCCIO") (class "Default")
      (node (ref "PCIE-NORTH") (pin "B14") (pinfunction "VCCIO_B14") (pintype "passive"))
    )
    (net (code "183") (name "Net-(C2-Pad1)") (class "Default")
      (node (ref "C2") (pin "1") (pinfunction "1_1") (pintype "passive"))
      (node (ref "X1") (pin "1") (pinfunction "1_1") (pintype "passive"))
    )
    (net (code "184") (name "Net-(C4-Pad2)") (class "Default")
      (node (ref "C4") (pin "2") (pinfunction "2_2") (pintype "passive"))
      (node (ref "R8") (pin "1") (pinfunction "1_1") (pintype "passive"))
    )
    (net (code "185") (name "Net-(C17-Pad2)") (class "Default")
      (node (ref "C17") (pin "2") (pinfunction "2_2") (pintype "passive"))
      (node (ref "X2") (pin "1") (pinfunction "1_1") (pintype "passive"))
    )
    (net (code "186") (name "Net-(C18-Pad2)") (class "Default")
      (node (ref "C18") (pin "2") (pinfunction "2_2") (pintype "passive"))
      (node (ref "R9") (pin "1") (pinfunction "1_1") (pintype "passive"))
    )
    (net (code "187") (name "Net-(C19-Pad2)") (class "Default")
      (node (ref "C19") (pin "2") (pinfunction "2_2") (pintype "passive"))
      (node (ref "R10") (pin "1") (pinfunction "1_1") (pintype "passive"))
    )
    (net (code "188") (name "Net-(C20-Pad2)") (class "Default")
      (node (ref "C20") (pin "2") (pinfunction "2_2") (pintype "passive"))
      (node (ref "R11") (pin "1") (pinfunction "1_1") (pintype "passive"))
    )
    (net (code "189") (name "Net-(C35-Pad2)") (class "Default")
      (node (ref "C35") (pin "2") (pinfunction "2_2") (pintype "passive"))
      (node (ref "X3") (pin "1") (pinfunction "1_1") (pintype "passive"))
    )
    (net (code "190") (name "Net-(C36-Pad2)") (class "Default")
      (node (ref "C36") (pin "2") (pinfunction "2_2") (pintype "passive"))
      (node (ref "R12") (pin "1") (pinfunction "1_1") (pintype "passive"))
    )
    (net (code "191") (name "Net-(C37-Pad2)") (class "Default")
      (node (ref "C37") (pin "2") (pinfunction "2_2") (pintype "passive"))
      (node (ref "R13") (pin "1") (pinfunction "1_1") (pintype "passive"))
    )
    (net (code "192") (name "Net-(C38-Pad2)") (class "Default")
      (node (ref "C38") (pin "2") (pinfunction "2_2") (pintype "passive"))
      (node (ref "R14") (pin "1") (pinfunction "1_1") (pintype "passive"))
    )
    (net (code "193") (name "Net-(D1-PadC)") (class "Default")
      (node (ref "D1") (pin "C") (pinfunction "C_C") (pintype "passive"))
      (node (ref "R4") (pin "2") (pinfunction "2_2") (pintype "passive"))
    )
    (net (code "194") (name "Net-(D2-PadC)") (class "Default")
      (node (ref "D2") (pin "C") (pinfunction "C_C") (pintype "passive"))
      (node (ref "R5") (pin "2") (pinfunction "2_2") (pintype "passive"))
    )
    (net (code "195") (name "Net-(D3-PadC)") (class "Default")
      (node (ref "D3") (pin "C") (pinfunction "C_C") (pintype "passive"))
      (node (ref "R6") (pin "2") (pinfunction "2_2") (pintype "passive"))
    )
    (net (code "196") (name "Net-(D4-PadC)") (class "Default")
      (node (ref "D4") (pin "C") (pinfunction "C_C") (pintype "passive"))
      (node (ref "R7") (pin "2") (pinfunction "2_2") (pintype "passive"))
    )
    (net (code "197") (name "Net-(U1-WP)") (class "Default")
      (node (ref "R1") (pin "2") (pinfunction "2_2") (pintype "passive"))
      (node (ref "R2") (pin "1") (pinfunction "1_1") (pintype "passive"))
      (node (ref "U1") (pin "7") (pinfunction "WP_7") (pintype "input"))
    )
    (net (code "198") (name "Net-(U2-LF+)") (class "Default")
      (node (ref "C3") (pin "1") (pinfunction "1_1") (pintype "passive"))
      (node (ref "U2") (pin "39") (pinfunction "LF+_39") (pintype "passive"))
    )
    (net (code "199") (name "Net-(U2-LF-)") (class "Default")
      (node (ref "C3") (pin "2") (pinfunction "2_2") (pintype "passive"))
      (node (ref "U2") (pin "40") (pinfunction "LF-_40") (pintype "passive"))
    )
    (net (code "200") (name "Net-(U2-SDI)") (class "Default")
      (node (ref "C2") (pin "2") (pinfunction "2_2") (pintype "passive"))
      (node (ref "U2") (pin "2") (pinfunction "SDI_2") (pintype "input"))
    )
    (net (code "201") (name "Net-(U2-SDI_TERM)") (class "Default")
      (node (ref "C4") (pin "1") (pinfunction "1_1") (pintype "passive"))
      (node (ref "U2") (pin "3") (pinfunction "SDI_TERM_3") (pintype "passive"))
    )
    (net (code "202") (name "Net-(U2-VCO_FILT)") (class "Default")
      (node (ref "C5") (pin "1") (pinfunction "1_1") (pintype "passive"))
      (node (ref "U2") (pin "34") (pinfunction "VCO_FILT_34") (pintype "passive"))
    )
    (net (code "203") (name "Net-(U2-VCO_FILT10)") (class "Default")
      (node (ref "C6") (pin "1") (pinfunction "1_1") (pintype "passive"))
      (node (ref "U2") (pin "30") (pinfunction "VCO_FILT10_30") (pintype "passive"))
    )
    (net (code "204") (name "Net-(U3-LF+)") (class "Default")
      (node (ref "C21") (pin "1") (pinfunction "1_1") (pintype "passive"))
      (node (ref "U3") (pin "39") (pinfunction "LF+_39") (pintype "passive"))
    )
    (net (code "205") (name "Net-(U3-LF-)") (class "Default")
      (node (ref "C21") (pin "2") (pinfunction "2_2") (pintype "passive"))
      (node (ref "U3") (pin "40") (pinfunction "LF-_40") (pintype "passive"))
    )
    (net (code "206") (name "Net-(U3-SDO0)") (class "Default")
      (node (ref "C17") (pin "1") (pinfunction "1_1") (pintype "passive"))
      (node (ref "U3") (pin "27") (pinfunction "SDO0_27") (pintype "output"))
    )
    (net (code "207") (name "Net-(U3-SDO1{slash}RCO)") (class "Default")
      (node (ref "C19") (pin "1") (pinfunction "1_1") (pintype "passive"))
      (node (ref "U3") (pin "23") (pinfunction "SDO1/RCO_23") (pintype "output"))
    )
    (net (code "208") (name "Net-(U3-TERM)") (class "Default")
      (node (ref "C22") (pin "1") (pinfunction "1_1") (pintype "passive"))
      (node (ref "U3") (pin "5") (pinfunction "TERM_5") (pintype "passive"))
    )
    (net (code "209") (name "Net-(U3-VCO_FILT)") (class "Default")
      (node (ref "C23") (pin "1") (pinfunction "1_1") (pintype "passive"))
      (node (ref "U3") (pin "34") (pinfunction "VCO_FILT_34") (pintype "passive"))
    )
    (net (code "210") (name "Net-(U3-VCO_FILT10)") (class "Default")
      (node (ref "C24") (pin "1") (pinfunction "1_1") (pintype "passive"))
      (node (ref "U3") (pin "30") (pinfunction "VCO_FILT10_30") (pintype "passive"))
    )
    (net (code "211") (name "Net-(U3-~{SDO0})") (class "Default")
      (node (ref "C20") (pin "1") (pinfunction "1_1") (pintype "passive"))
      (node (ref "U3") (pin "26") (pinfunction "~{SDO0}_26") (pintype "output"))
    )
    (net (code "212") (name "Net-(U3-~{SDO1}{slash}~{RCO})") (class "Default")
      (node (ref "C18") (pin "1") (pinfunction "1_1") (pintype "passive"))
      (node (ref "U3") (pin "22") (pinfunction "~{SDO1}/~{RCO}_22") (pintype "output"))
    )
    (net (code "213") (name "Net-(U4-LF+)") (class "Default")
      (node (ref "C39") (pin "1") (pinfunction "1_1") (pintype "passive"))
      (node (ref "U4") (pin "39") (pinfunction "LF+_39") (pintype "passive"))
    )
    (net (code "214") (name "Net-(U4-LF-)") (class "Default")
      (node (ref "C39") (pin "2") (pinfunction "2_2") (pintype "passive"))
      (node (ref "U4") (pin "40") (pinfunction "LF-_40") (pintype "passive"))
    )
    (net (code "215") (name "Net-(U4-SDO0)") (class "Default")
      (node (ref "C37") (pin "1") (pinfunction "1_1") (pintype "passive"))
      (node (ref "U4") (pin "27") (pinfunction "SDO0_27") (pintype "output"))
    )
    (net (code "216") (name "Net-(U4-SDO1{slash}RCO)") (class "Default")
      (node (ref "C35") (pin "1") (pinfunction "1_1") (pintype "passive"))
      (node (ref "U4") (pin "23") (pinfunction "SDO1/RCO_23") (pintype "output"))
    )
    (net (code "217") (name "Net-(U4-TERM)") (class "Default")
      (node (ref "C40") (pin "1") (pinfunction "1_1") (pintype "passive"))
      (node (ref "U4") (pin "5") (pinfunction "TERM_5") (pintype "passive"))
    )
    (net (code "218") (name "Net-(U4-VCO_FILT)") (class "Default")
      (node (ref "C41") (pin "1") (pinfunction "1_1") (pintype "passive"))
      (node (ref "U4") (pin "34") (pinfunction "VCO_FILT_34") (pintype "passive"))
    )
    (net (code "219") (name "Net-(U4-VCO_FILT10)") (class "Default")
      (node (ref "C42") (pin "1") (pinfunction "1_1") (pintype "passive"))
      (node (ref "U4") (pin "30") (pinfunction "VCO_FILT10_30") (pintype "passive"))
    )
    (net (code "220") (name "Net-(U4-~{SDO0})") (class "Default")
      (node (ref "C38") (pin "1") (pinfunction "1_1") (pintype "passive"))
      (node (ref "U4") (pin "26") (pinfunction "~{SDO0}_26") (pintype "output"))
    )
    (net (code "221") (name "Net-(U4-~{SDO1}{slash}~{RCO})") (class "Default")
      (node (ref "C36") (pin "1") (pinfunction "1_1") (pintype "passive"))
      (node (ref "U4") (pin "22") (pinfunction "~{SDO1}/~{RCO}_22") (pintype "output"))
    )
    (net (code "222") (name "Net-(U5-OUT+)") (class "Default")
      (node (ref "C54") (pin "1") (pinfunction "1_1") (pintype "passive"))
      (node (ref "R15") (pin "1") (pinfunction "1_1") (pintype "passive"))
      (node (ref "U5") (pin "4") (pinfunction "OUT+_4") (pintype "output"))
    )
    (net (code "223") (name "Net-(U5-OUT-)") (class "Default")
      (node (ref "C55") (pin "1") (pinfunction "1_1") (pintype "passive"))
      (node (ref "R15") (pin "2") (pinfunction "2_2") (pintype "passive"))
      (node (ref "U5") (pin "5") (pinfunction "OUT-_5") (pintype "output"))
    )
    (net (code "224") (name "PG_A") (class "Default")
      (node (ref "U6") (pin "2") (pinfunction "PG_2") (pintype "power_in"))
    )
    (net (code "225") (name "PG_B") (class "Default")
      (node (ref "U9") (pin "2") (pinfunction "PG_2") (pintype "power_in"))
    )
    (net (code "226") (name "PROG_B") (class "Default")
      (node (ref "JM1") (pin "94") (pinfunction "94_94") (pintype "bidirectional"))
    )
    (net (code "227") (name "SCL") (class "Default")
      (node (ref "PCIE-NORTH") (pin "B2") (pinfunction "SCL_B2") (pintype "passive"))
      (node (ref "U1") (pin "6") (pinfunction "SCL_6") (pintype "input"))
    )
    (net (code "228") (name "SDA") (class "Default")
      (node (ref "PCIE-NORTH") (pin "B1") (pinfunction "SDA_B1") (pintype "passive"))
      (node (ref "U1") (pin "5") (pinfunction "SDA_5") (pintype "bidirectional"))
    )
    (net (code "229") (name "SPI-CLK") (class "Default")
      (node (ref "JM2") (pin "67") (pinfunction "67_67") (pintype "bidirectional"))
    )
    (net (code "230") (name "SPI-CS") (class "Default")
      (node (ref "JM2") (pin "69") (pinfunction "69_69") (pintype "bidirectional"))
    )
    (net (code "231") (name "SPI-DQ0") (class "Default")
      (node (ref "JM2") (pin "68") (pinfunction "68_68") (pintype "bidirectional"))
    )
    (net (code "232") (name "SPI-DQ1") (class "Default")
      (node (ref "JM2") (pin "71") (pinfunction "71_71") (pintype "bidirectional"))
    )
    (net (code "233") (name "SPI-DQ2") (class "Default")
      (node (ref "JM2") (pin "73") (pinfunction "73_73") (pintype "bidirectional"))
    )
    (net (code "234") (name "SPI-DQ3") (class "Default")
      (node (ref "JM2") (pin "70") (pinfunction "70_70") (pintype "bidirectional"))
    )
    (net (code "235") (name "S_5V") (class "Default")
      (node (ref "JP2") (pin "1") (pinfunction "1_1") (pintype "passive"))
      (node (ref "PCIE-SOUTH") (pin "B12") (pinfunction "5V_B12") (pintype "passive"))
    )
    (net (code "236") (name "S_PCIE_V") (class "Default")
      (node (ref "PCIE-SOUTH") (pin "B13") (pinfunction "VCC_B13") (pintype "passive"))
    )
    (net (code "237") (name "S_VCCIO") (class "Default")
      (node (ref "PCIE-SOUTH") (pin "B14") (pinfunction "VCCIO_B14") (pintype "passive"))
    )
    (net (code "238") (name "TCK") (class "Default")
      (node (ref "JM1") (pin "90") (pinfunction "90_90") (pintype "bidirectional"))
      (node (ref "JP1") (pin "6") (pinfunction "6_6") (pintype "passive"))
    )
    (net (code "239") (name "TDI") (class "Default")
      (node (ref "JM1") (pin "86") (pinfunction "86_86") (pintype "bidirectional"))
      (node (ref "JP1") (pin "10") (pinfunction "10_10") (pintype "passive"))
    )
    (net (code "240") (name "TDO") (class "Default")
      (node (ref "JM1") (pin "88") (pinfunction "88_88") (pintype "bidirectional"))
      (node (ref "JP1") (pin "8") (pinfunction "8_8") (pintype "passive"))
    )
    (net (code "241") (name "TMS") (class "Default")
      (node (ref "JM1") (pin "92") (pinfunction "92_92") (pintype "bidirectional"))
      (node (ref "JP1") (pin "4") (pinfunction "4_4") (pintype "passive"))
    )
    (net (code "242") (name "VCCIO0") (class "Default")
      (node (ref "JM2") (pin "53") (pinfunction "53_53") (pintype "bidirectional"))
      (node (ref "JP1") (pin "2") (pinfunction "2_2") (pintype "passive"))
    )
    (net (code "243") (name "VCCIO14") (class "Default")
      (node (ref "JM1") (pin "83") (pinfunction "83_83") (pintype "bidirectional"))
    )
    (net (code "244") (name "VCCIO15") (class "Default")
      (node (ref "JM2") (pin "54") (pinfunction "54_54") (pintype "bidirectional"))
    )
    (net (code "245") (name "VCCIO34") (class "Default")
      (node (ref "JM1") (pin "61") (pinfunction "61_61") (pintype "bidirectional"))
    )
    (net (code "246") (name "VCCO_4") (class "Default")
      (node (ref "C14") (pin "1") (pinfunction "1_1") (pintype "passive"))
      (node (ref "C15") (pin "1") (pinfunction "1_1") (pintype "passive"))
      (node (ref "C16") (pin "1") (pinfunction "1_1") (pintype "passive"))
      (node (ref "FB3") (pin "2") (pinfunction "2_2") (pintype "passive"))
      (node (ref "U2") (pin "24") (pinfunction "VCCO_1_24") (pintype "power_in"))
      (node (ref "U2") (pin "25") (pinfunction "VCCO_0_25") (pintype "power_in"))
    )
    (net (code "247") (name "VCCO_8") (class "Default")
      (node (ref "C32") (pin "1") (pinfunction "1_1") (pintype "passive"))
      (node (ref "C33") (pin "1") (pinfunction "1_1") (pintype "passive"))
      (node (ref "C34") (pin "1") (pinfunction "1_1") (pintype "passive"))
      (node (ref "FB6") (pin "2") (pinfunction "2_2") (pintype "passive"))
      (node (ref "U3") (pin "24") (pinfunction "VCCO_1_24") (pintype "power_in"))
      (node (ref "U3") (pin "25") (pinfunction "VCCO_0_25") (pintype "power_in"))
    )
    (net (code "248") (name "VCCO_9") (class "Default")
      (node (ref "C50") (pin "1") (pinfunction "1_1") (pintype "passive"))
      (node (ref "C51") (pin "1") (pinfunction "1_1") (pintype "passive"))
      (node (ref "C52") (pin "1") (pinfunction "1_1") (pintype "passive"))
      (node (ref "FB9") (pin "2") (pinfunction "2_2") (pintype "passive"))
      (node (ref "U4") (pin "24") (pinfunction "VCCO_1_24") (pintype "power_in"))
      (node (ref "U4") (pin "25") (pinfunction "VCCO_0_25") (pintype "power_in"))
    )
    (net (code "249") (name "VCC_4") (class "Default")
      (node (ref "C11") (pin "1") (pinfunction "1_1") (pintype "passive"))
      (node (ref "C12") (pin "1") (pinfunction "1_1") (pintype "passive"))
      (node (ref "C13") (pin "1") (pinfunction "1_1") (pintype "passive"))
      (node (ref "FB2") (pin "2") (pinfunction "2_2") (pintype "passive"))
      (node (ref "U2") (pin "35") (pinfunction "VCC_CORE_35") (pintype "power_in"))
      (node (ref "U2") (pin "4") (pinfunction "VCC_SDI_4") (pintype "power_in"))
    )
    (net (code "250") (name "VCC_8") (class "Default")
      (node (ref "C29") (pin "1") (pinfunction "1_1") (pintype "passive"))
      (node (ref "C30") (pin "1") (pinfunction "1_1") (pintype "passive"))
      (node (ref "C31") (pin "1") (pinfunction "1_1") (pintype "passive"))
      (node (ref "FB5") (pin "2") (pinfunction "2_2") (pintype "passive"))
      (node (ref "U3") (pin "35") (pinfunction "VCC_CORE_35") (pintype "power_in"))
      (node (ref "U3") (pin "4") (pinfunction "VCC_DDI_4") (pintype "power_in"))
    )
    (net (code "251") (name "VCC_9") (class "Default")
      (node (ref "C47") (pin "1") (pinfunction "1_1") (pintype "passive"))
      (node (ref "C48") (pin "1") (pinfunction "1_1") (pintype "passive"))
      (node (ref "C49") (pin "1") (pinfunction "1_1") (pintype "passive"))
      (node (ref "FB8") (pin "2") (pinfunction "2_2") (pintype "passive"))
      (node (ref "U4") (pin "35") (pinfunction "VCC_CORE_35") (pintype "power_in"))
      (node (ref "U4") (pin "4") (pinfunction "VCC_DDI_4") (pintype "power_in"))
    )
    (net (code "252") (name "VDD_4") (class "Default")
      (node (ref "C10") (pin "1") (pinfunction "1_1") (pintype "passive"))
      (node (ref "C7") (pin "1") (pinfunction "1_1") (pintype "passive"))
      (node (ref "C8") (pin "1") (pinfunction "1_1") (pintype "passive"))
      (node (ref "C9") (pin "1") (pinfunction "1_1") (pintype "passive"))
      (node (ref "FB1") (pin "2") (pinfunction "2_2") (pintype "passive"))
      (node (ref "U2") (pin "16") (pinfunction "VDD_16") (pintype "power_in"))
      (node (ref "U2") (pin "20") (pinfunction "VCCO1V8_1_20") (pintype "power_in"))
      (node (ref "U2") (pin "29") (pinfunction "VCCO1V8_0_29") (pintype "power_in"))
    )
    (net (code "253") (name "VDD_8") (class "Default")
      (node (ref "C25") (pin "1") (pinfunction "1_1") (pintype "passive"))
      (node (ref "C26") (pin "1") (pinfunction "1_1") (pintype "passive"))
      (node (ref "C27") (pin "1") (pinfunction "1_1") (pintype "passive"))
      (node (ref "C28") (pin "1") (pinfunction "1_1") (pintype "passive"))
      (node (ref "FB4") (pin "2") (pinfunction "2_2") (pintype "passive"))
      (node (ref "U3") (pin "16") (pinfunction "VDD_16") (pintype "power_in"))
      (node (ref "U3") (pin "20") (pinfunction "VCCO1V8_1_20") (pintype "power_in"))
      (node (ref "U3") (pin "29") (pinfunction "VCCO1V8_0_29") (pintype "power_in"))
    )
    (net (code "254") (name "VDD_9") (class "Default")
      (node (ref "C43") (pin "1") (pinfunction "1_1") (pintype "passive"))
      (node (ref "C44") (pin "1") (pinfunction "1_1") (pintype "passive"))
      (node (ref "C45") (pin "1") (pinfunction "1_1") (pintype "passive"))
      (node (ref "C46") (pin "1") (pinfunction "1_1") (pintype "passive"))
      (node (ref "FB7") (pin "2") (pinfunction "2_2") (pintype "passive"))
      (node (ref "U4") (pin "16") (pinfunction "VDD_16") (pintype "power_in"))
      (node (ref "U4") (pin "20") (pinfunction "VCCO1V8_1_20") (pintype "power_in"))
      (node (ref "U4") (pin "29") (pinfunction "VCCO1V8_0_29") (pintype "power_in"))
    )
    (net (code "255") (name "VOUT_A") (class "Default")
      (node (ref "C56") (pin "1") (pinfunction "1_1") (pintype "passive"))
      (node (ref "FB10") (pin "1") (pinfunction "1_1") (pintype "passive"))
      (node (ref "R18") (pin "2") (pinfunction "2_2") (pintype "passive"))
      (node (ref "U6") (pin "8") (pinfunction "VOUT_8") (pintype "output"))
    )
    (net (code "256") (name "VOUT_B") (class "Default")
      (node (ref "C58") (pin "1") (pinfunction "1_1") (pintype "passive"))
      (node (ref "FB11") (pin "1") (pinfunction "1_1") (pintype "passive"))
      (node (ref "R16") (pin "2") (pinfunction "2_2") (pintype "passive"))
      (node (ref "U9") (pin "8") (pinfunction "VOUT_8") (pintype "output"))
    )
    (net (code "257") (name "VSUP") (class "Default")
      (node (ref "C57") (pin "1") (pinfunction "1_1") (pintype "passive"))
      (node (ref "C59") (pin "1") (pinfunction "1_1") (pintype "passive"))
      (node (ref "JP2") (pin "2") (pinfunction "2_2") (pintype "passive"))
      (node (ref "U6") (pin "3") (pinfunction "VIN_3") (pintype "power_in"))
      (node (ref "U6") (pin "4") (pinfunction "VIN_4") (pintype "power_in"))
      (node (ref "U9") (pin "3") (pinfunction "VIN_3") (pintype "power_in"))
      (node (ref "U9") (pin "4") (pinfunction "VIN_4") (pintype "power_in"))
    )
    (net (code "258") (name "VXX") (class "Default")
      (node (ref "C53") (pin "1") (pinfunction "1_1") (pintype "passive"))
      (node (ref "FB17") (pin "2") (pinfunction "2_2") (pintype "passive"))
      (node (ref "U5") (pin "6") (pinfunction "VCC_6") (pintype "power_in"))
    )
    (net (code "259") (name "unconnected-(JP1-Pad12)") (class "Default")
      (node (ref "JP1") (pin "12") (pinfunction "12_12") (pintype "passive"))
    )
    (net (code "260") (name "unconnected-(JP1-Pad14)") (class "Default")
      (node (ref "JP1") (pin "14") (pinfunction "14_14") (pintype "passive"))
    )
    (net (code "261") (name "unconnected-(PCIE-NORTH-PWRGD-PadA11)") (class "Default")
      (node (ref "PCIE-NORTH") (pin "A11") (pinfunction "PWRGD_A11") (pintype "passive"))
    )
    (net (code "262") (name "unconnected-(PCIE-SOUTH-PWRGD-PadA11)") (class "Default")
      (node (ref "PCIE-SOUTH") (pin "A11") (pinfunction "PWRGD_A11") (pintype "passive"))
    )
    (net (code "263") (name "unconnected-(PCIE-SOUTH-SCL-PadB2)") (class "Default")
      (node (ref "PCIE-SOUTH") (pin "B2") (pinfunction "SCL_B2") (pintype "passive"))
    )
    (net (code "264") (name "unconnected-(PCIE-SOUTH-SDA-PadB1)") (class "Default")
      (node (ref "PCIE-SOUTH") (pin "B1") (pinfunction "SDA_B1") (pintype "passive"))
    )
    (net (code "265") (name "unconnected-(PCIE-SOUTH-V_I2C-PadB3)") (class "Default")
      (node (ref "PCIE-SOUTH") (pin "B3") (pinfunction "V_I2C_B3") (pintype "passive"))
    )
  )
)
